# boron-v1_00.net
KiCad netlist of a schematic drawn in EAGLE
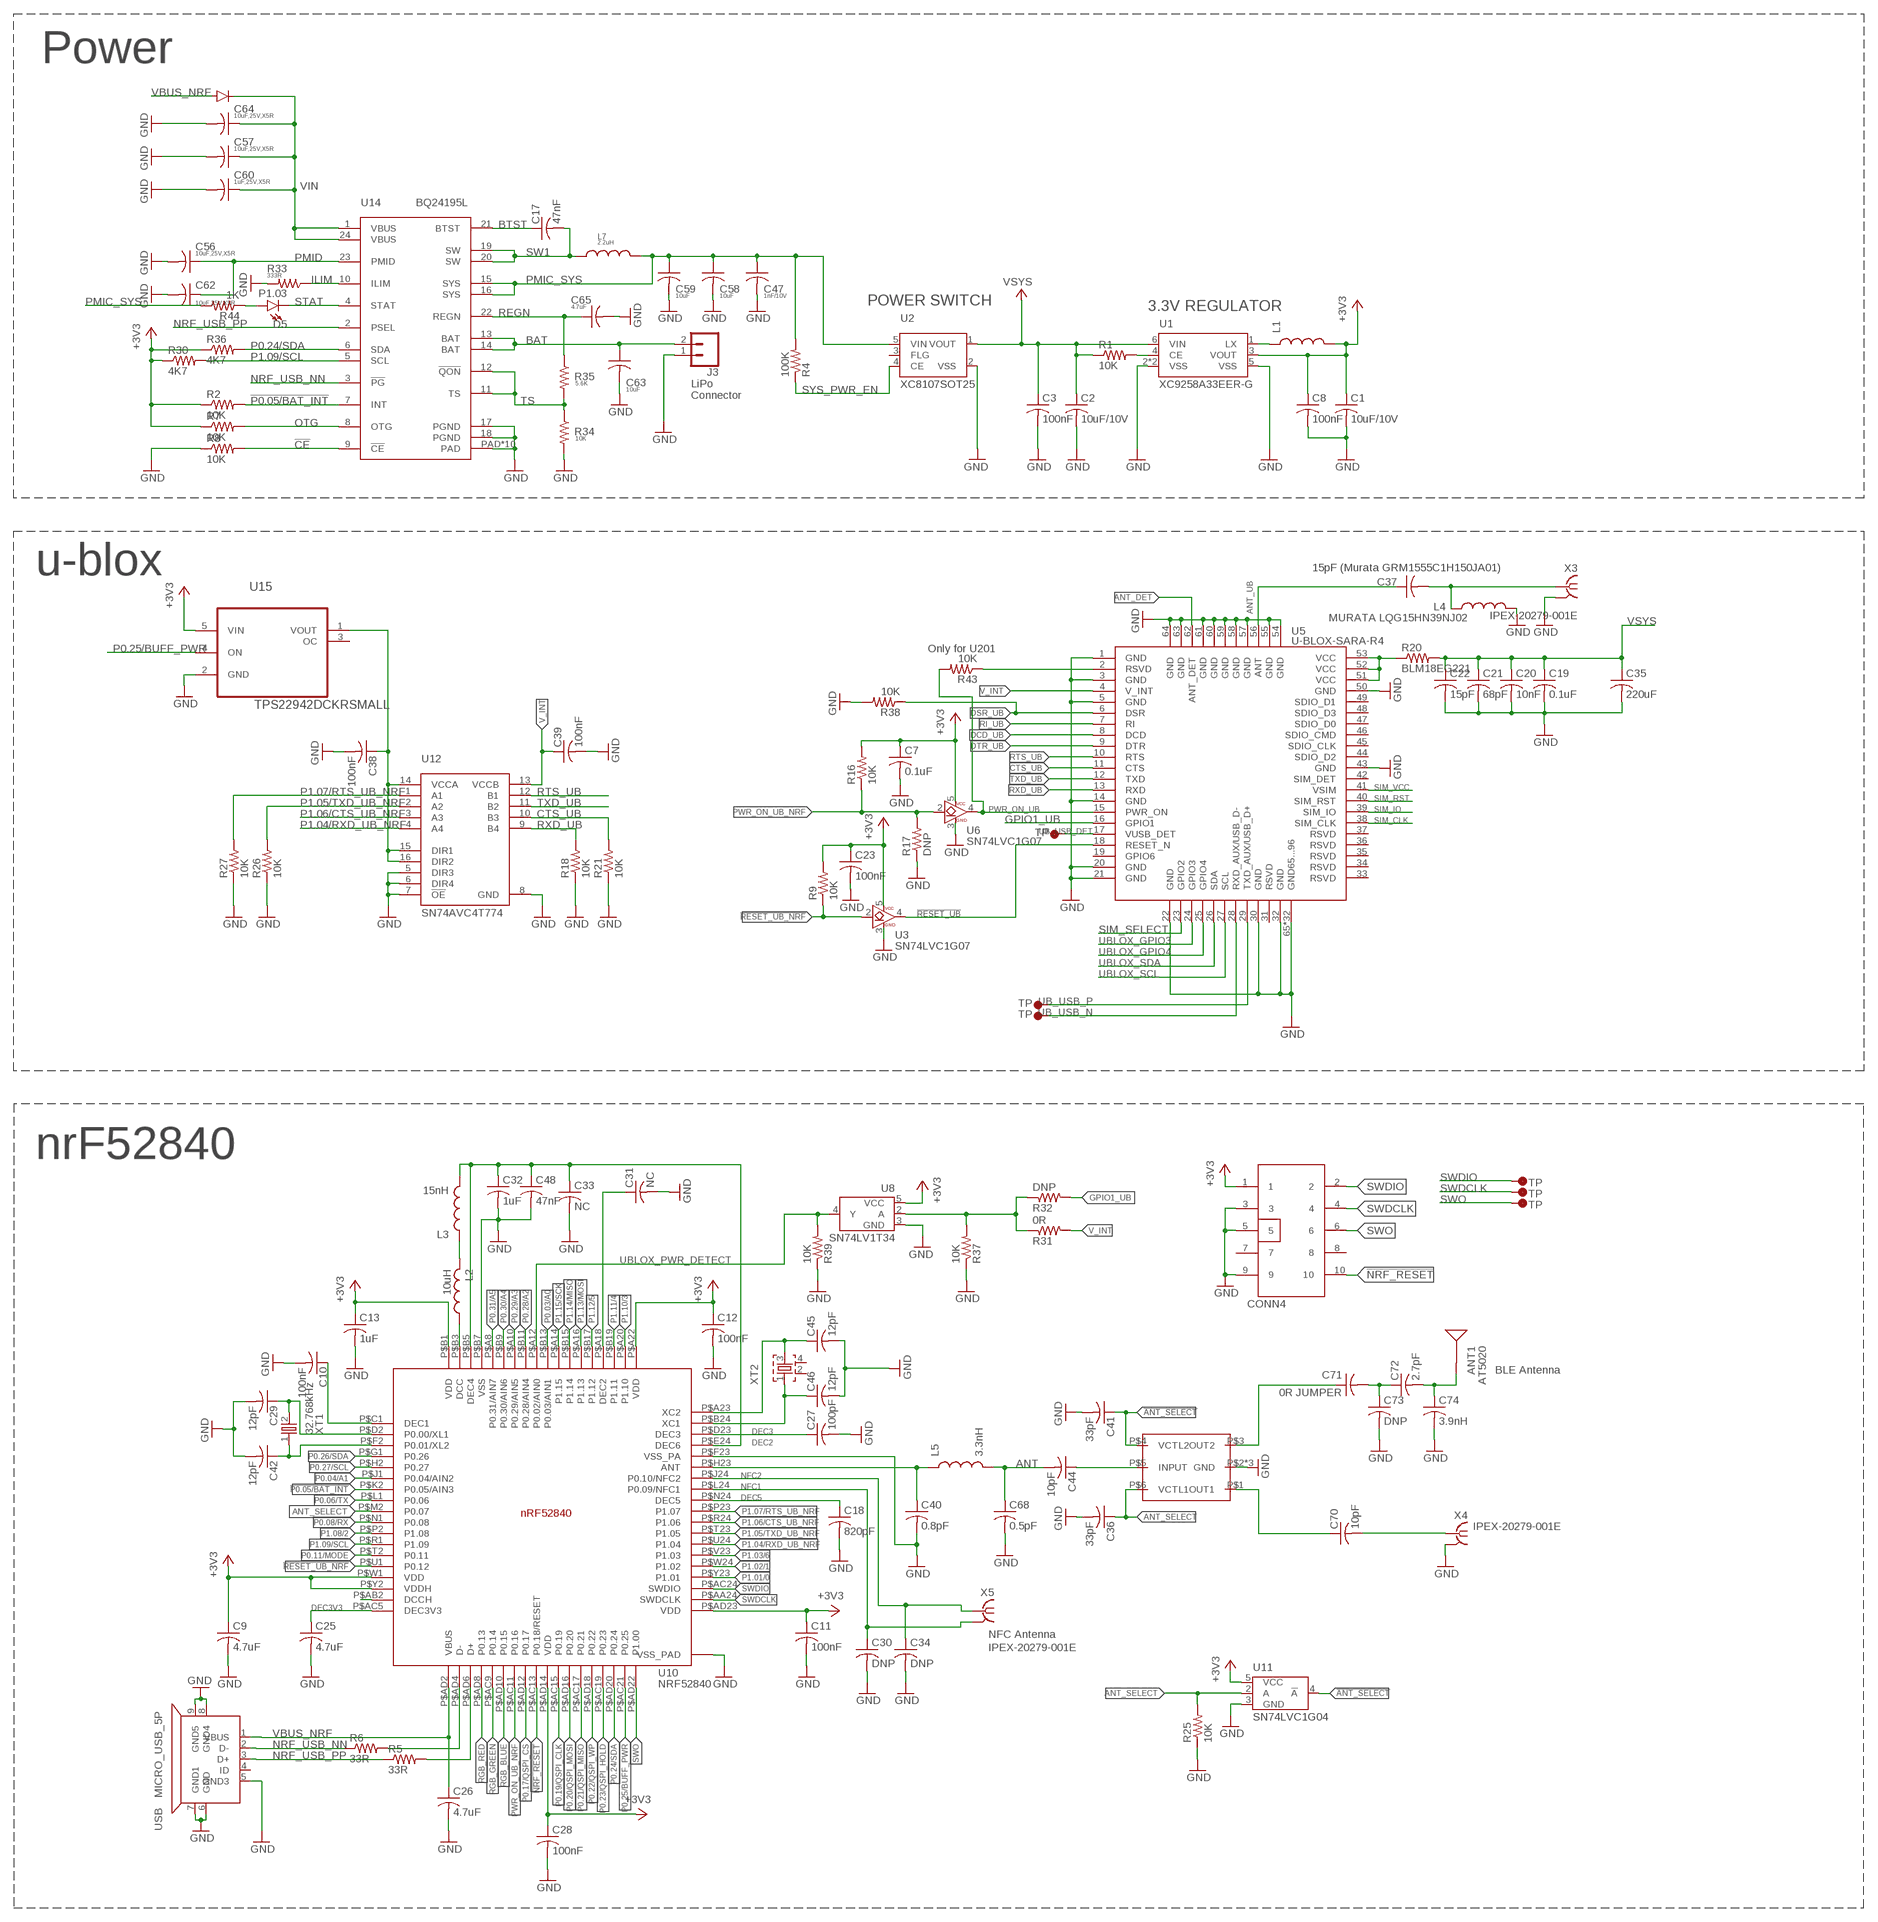
[diagram p0: schematic, sheet 1, part 1 of 2]
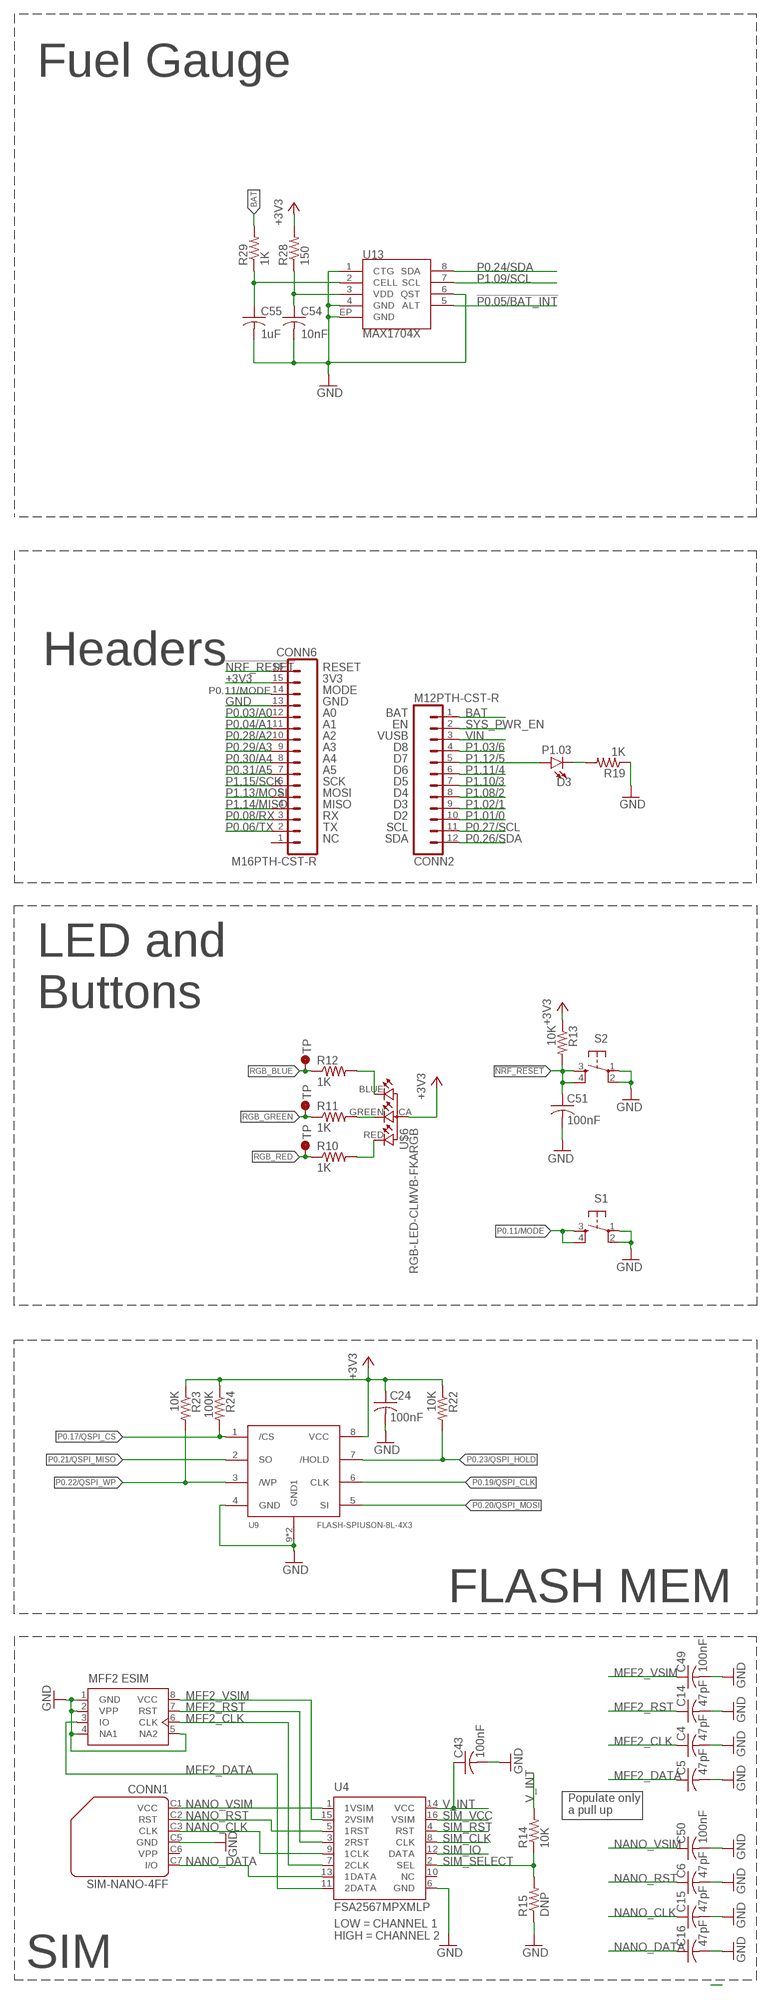
[diagram p1: schematic, sheet 1, part 2 of 2]

(export (version "E")
  (design (tool "Eeschema 10.0.6"))
  (components
    (comp (ref "ANT1")
      (value "AT5020")
      (footprint "eagle-import:AT5020")
      (libsource (lib "eagle-import") (part "AT5020"))
    )
    (comp (ref "C1")
      (value "10uF/10V")
      (footprint "eagle-import:C0603K")
      (libsource (lib "eagle-import") (part "C-USC0603K"))
    )
    (comp (ref "C2")
      (value "10uF/10V")
      (footprint "eagle-import:C0603K")
      (libsource (lib "eagle-import") (part "C-USC0603K"))
    )
    (comp (ref "C3")
      (value "100nF")
      (footprint "eagle-import:C0603K")
      (libsource (lib "eagle-import") (part "C-USC0603K"))
    )
    (comp (ref "C4")
      (value "47pF")
      (footprint "eagle-import:C0201_B")
      (libsource (lib "eagle-import") (part "C-USC0201_B"))
    )
    (comp (ref "C5")
      (value "47pF")
      (footprint "eagle-import:C0201_B")
      (libsource (lib "eagle-import") (part "C-USC0201_B"))
    )
    (comp (ref "C6")
      (value "47pF")
      (footprint "eagle-import:C0201_B")
      (libsource (lib "eagle-import") (part "C-USC0201_B"))
    )
    (comp (ref "C7")
      (value "0.1uF")
      (footprint "eagle-import:C0402_B")
      (libsource (lib "eagle-import") (part "Spark_C-US"))
    )
    (comp (ref "C8")
      (value "100nF")
      (footprint "eagle-import:C0201_B")
      (libsource (lib "eagle-import") (part "C-USC0201_B"))
    )
    (comp (ref "C9")
      (value "4.7uF")
      (footprint "eagle-import:C0402")
      (libsource (lib "eagle-import") (part "C-USC0402"))
    )
    (comp (ref "C10")
      (value "100nF")
      (footprint "eagle-import:C0201_B")
      (libsource (lib "eagle-import") (part "C-USC0201_B"))
    )
    (comp (ref "C11")
      (value "100nF")
      (footprint "eagle-import:C0201_B")
      (libsource (lib "eagle-import") (part "C-USC0201_B"))
    )
    (comp (ref "C12")
      (value "100nF")
      (footprint "eagle-import:C0201_B")
      (libsource (lib "eagle-import") (part "C-USC0201_B"))
    )
    (comp (ref "C13")
      (value "1uF")
      (footprint "eagle-import:C0402")
      (libsource (lib "eagle-import") (part "C-USC0402"))
    )
    (comp (ref "C14")
      (value "47pF")
      (footprint "eagle-import:C0201_B")
      (libsource (lib "eagle-import") (part "C-USC0201_B"))
    )
    (comp (ref "C15")
      (value "47pF")
      (footprint "eagle-import:C0201_B")
      (libsource (lib "eagle-import") (part "C-USC0201_B"))
    )
    (comp (ref "C16")
      (value "47pF")
      (footprint "eagle-import:C0201_B")
      (libsource (lib "eagle-import") (part "C-USC0201_B"))
    )
    (comp (ref "C17")
      (value "47nF")
      (footprint "eagle-import:C0201_B")
      (libsource (lib "eagle-import") (part "C-USC0201_B"))
    )
    (comp (ref "C18")
      (value "820pF")
      (footprint "eagle-import:C0201_B")
      (libsource (lib "eagle-import") (part "C-USC0201_B"))
    )
    (comp (ref "C19")
      (value "0.1uF")
      (footprint "eagle-import:C0402_B")
      (libsource (lib "eagle-import") (part "Spark_C-US"))
    )
    (comp (ref "C20")
      (value "10nF")
      (footprint "eagle-import:C0402_B")
      (libsource (lib "eagle-import") (part "Spark_C-US"))
    )
    (comp (ref "C21")
      (value "68pF")
      (footprint "eagle-import:C0402_B")
      (libsource (lib "eagle-import") (part "Spark_C-US"))
    )
    (comp (ref "C22")
      (value "15pF")
      (footprint "eagle-import:C0402_B")
      (libsource (lib "eagle-import") (part "Spark_C-US"))
    )
    (comp (ref "C23")
      (value "100nF")
      (footprint "eagle-import:C0201_B")
      (libsource (lib "eagle-import") (part "C-USC0201_B"))
    )
    (comp (ref "C24")
      (value "100nF")
      (footprint "eagle-import:C0201_B")
      (libsource (lib "eagle-import") (part "C-USC0201_B"))
    )
    (comp (ref "C25")
      (value "4.7uF")
      (footprint "eagle-import:C0402")
      (libsource (lib "eagle-import") (part "C-USC0402"))
    )
    (comp (ref "C26")
      (value "4.7uF")
      (footprint "eagle-import:C0402")
      (libsource (lib "eagle-import") (part "C-USC0402"))
    )
    (comp (ref "C27")
      (value "100pF")
      (footprint "eagle-import:C0201_B")
      (libsource (lib "eagle-import") (part "C-USC0201_B"))
    )
    (comp (ref "C28")
      (value "100nF")
      (footprint "eagle-import:C0201_B")
      (libsource (lib "eagle-import") (part "C-USC0201_B"))
    )
    (comp (ref "C29")
      (value "12pF")
      (footprint "eagle-import:C0201_B")
      (libsource (lib "eagle-import") (part "C-USC0201_B"))
    )
    (comp (ref "C30")
      (value "DNP")
      (footprint "eagle-import:C0201_B")
      (libsource (lib "eagle-import") (part "C-USC0201_B"))
    )
    (comp (ref "C31")
      (value "NC")
      (footprint "eagle-import:C0201_B")
      (libsource (lib "eagle-import") (part "C-USC0201_B"))
    )
    (comp (ref "C32")
      (value "1uF")
      (footprint "eagle-import:C0402K")
      (libsource (lib "eagle-import") (part "C-USC0402K"))
    )
    (comp (ref "C33")
      (value "NC")
      (footprint "eagle-import:C0201_B")
      (libsource (lib "eagle-import") (part "C-USC0201_B"))
    )
    (comp (ref "C34")
      (value "DNP")
      (footprint "eagle-import:C0201_B")
      (libsource (lib "eagle-import") (part "C-USC0201_B"))
    )
    (comp (ref "C35")
      (value "220uF")
      (footprint "eagle-import:C1210")
      (libsource (lib "eagle-import") (part "C-USC1210"))
    )
    (comp (ref "C36")
      (value "33pF")
      (footprint "eagle-import:C0201_B")
      (libsource (lib "eagle-import") (part "C-USC0201_B"))
    )
    (comp (ref "C37")
      (value "15pF (Murata GRM1555C1H150JA01)")
      (footprint "eagle-import:C0402_B")
      (libsource (lib "eagle-import") (part "Spark_C-US"))
    )
    (comp (ref "C38")
      (value "100nF")
      (footprint "eagle-import:C0201_B")
      (libsource (lib "eagle-import") (part "C-USC0201_B"))
    )
    (comp (ref "C39")
      (value "100nF")
      (footprint "eagle-import:C0201_B")
      (libsource (lib "eagle-import") (part "C-USC0201_B"))
    )
    (comp (ref "C40")
      (value "0.8pF")
      (footprint "eagle-import:C0201_B")
      (libsource (lib "eagle-import") (part "C-USC0201_B"))
    )
    (comp (ref "C41")
      (value "33pF")
      (footprint "eagle-import:C0201_B")
      (libsource (lib "eagle-import") (part "C-USC0201_B"))
    )
    (comp (ref "C42")
      (value "12pF")
      (footprint "eagle-import:C0201_B")
      (libsource (lib "eagle-import") (part "C-USC0201_B"))
    )
    (comp (ref "C43")
      (value "100nF")
      (footprint "eagle-import:C0201_B")
      (libsource (lib "eagle-import") (part "C-USC0201_B"))
    )
    (comp (ref "C44")
      (value "10pF")
      (footprint "eagle-import:C0201_B")
      (libsource (lib "eagle-import") (part "C-USC0201_B"))
    )
    (comp (ref "C45")
      (value "12pF")
      (footprint "eagle-import:C0201_B")
      (libsource (lib "eagle-import") (part "C-USC0201_B"))
    )
    (comp (ref "C46")
      (value "12pF")
      (footprint "eagle-import:C0201_B")
      (libsource (lib "eagle-import") (part "C-USC0201_B"))
    )
    (comp (ref "C47")
      (value "1nF/10V")
      (footprint "eagle-import:C0402_B")
      (libsource (lib "eagle-import") (part "C-US0402"))
    )
    (comp (ref "C48")
      (value "47nF")
      (footprint "eagle-import:C0201_B")
      (libsource (lib "eagle-import") (part "C-USC0201_B"))
    )
    (comp (ref "C49")
      (value "100nF")
      (footprint "eagle-import:C0201_B")
      (libsource (lib "eagle-import") (part "C-USC0201_B"))
    )
    (comp (ref "C50")
      (value "100nF")
      (footprint "eagle-import:C0201_B")
      (libsource (lib "eagle-import") (part "C-USC0201_B"))
    )
    (comp (ref "C51")
      (value "100nF")
      (footprint "eagle-import:C0201_B")
      (libsource (lib "eagle-import") (part "C-USC0201_B"))
    )
    (comp (ref "C54")
      (value "10nF")
      (footprint "eagle-import:C0402_B")
      (libsource (lib "eagle-import") (part "Spark_C-US"))
    )
    (comp (ref "C55")
      (value "1uF")
      (footprint "eagle-import:C0402_B")
      (libsource (lib "eagle-import") (part "Spark_C-US"))
    )
    (comp (ref "C56")
      (value "10uF,25V,X5R")
      (footprint "eagle-import:C0603_B")
      (libsource (lib "eagle-import") (part "C-US0603"))
    )
    (comp (ref "C57")
      (value "10uF,25V,X5R")
      (footprint "eagle-import:C0603_B")
      (libsource (lib "eagle-import") (part "C-US0603"))
    )
    (comp (ref "C58")
      (value "10uF")
      (footprint "eagle-import:C0603_B")
      (libsource (lib "eagle-import") (part "C-US0603"))
    )
    (comp (ref "C59")
      (value "10uF")
      (footprint "eagle-import:C0603_B")
      (libsource (lib "eagle-import") (part "C-US0603"))
    )
    (comp (ref "C60")
      (value "1uF,25V,X5R")
      (footprint "eagle-import:C0603_B")
      (libsource (lib "eagle-import") (part "C-US0603"))
    )
    (comp (ref "C62")
      (value "10uF,25V,X5R")
      (footprint "eagle-import:C0603_B")
      (libsource (lib "eagle-import") (part "C-US0603"))
    )
    (comp (ref "C63")
      (value "10uF")
      (footprint "eagle-import:C0603_B")
      (libsource (lib "eagle-import") (part "C-US0603"))
    )
    (comp (ref "C64")
      (value "10uF,25V,X5R")
      (footprint "eagle-import:C0603_B")
      (libsource (lib "eagle-import") (part "C-US0603"))
    )
    (comp (ref "C65")
      (value "4.7uF")
      (footprint "eagle-import:C0603_B")
      (libsource (lib "eagle-import") (part "C-US0603"))
    )
    (comp (ref "C68")
      (value "0.5pF")
      (footprint "eagle-import:C0201_B")
      (libsource (lib "eagle-import") (part "C-USC0201_B"))
    )
    (comp (ref "C70")
      (value "10pF")
      (footprint "eagle-import:C0201_B")
      (libsource (lib "eagle-import") (part "C-USC0201_B"))
    )
    (comp (ref "C71")
      (value "0R JUMPER")
      (footprint "eagle-import:C0201_B")
      (libsource (lib "eagle-import") (part "C-USC0201_B"))
    )
    (comp (ref "C72")
      (value "2.7pF")
      (footprint "eagle-import:C0201_B")
      (libsource (lib "eagle-import") (part "C-USC0201_B"))
    )
    (comp (ref "C73")
      (value "DNP")
      (footprint "eagle-import:C0201_B")
      (libsource (lib "eagle-import") (part "C-USC0201_B"))
    )
    (comp (ref "C74")
      (value "3.9nH")
      (footprint "eagle-import:C0201_B")
      (libsource (lib "eagle-import") (part "C-USC0201_B"))
    )
    (comp (ref "CONN1")
      (value "SIM-NANO-4FF")
      (footprint "eagle-import:GCT-SIM8100")
      (libsource (lib "eagle-import") (part "SIM-NANO-4FF"))
    )
    (comp (ref "CONN2")
      (value "M12PTH-CST-R")
      (footprint "eagle-import:1X12-CASTELLATED")
      (libsource (lib "eagle-import") (part "M12PTH-CST-R"))
    )
    (comp (ref "CONN4")
      (value "CONN5X2")
      (footprint "eagle-import:CONN5X2_1.27")
      (libsource (lib "eagle-import") (part "CONN5X2"))
    )
    (comp (ref "CONN6")
      (value "M16PTH-CST-R")
      (footprint "eagle-import:1X16-CASTELLATED")
      (libsource (lib "eagle-import") (part "M16PTH-CST-R"))
    )
    (comp (ref "D3")
      (value "P1.03")
      (footprint "eagle-import:LED-0603")
      (libsource (lib "eagle-import") (part "LED-RED0603"))
    )
    (comp (ref "D4")
      (value "DIODE_NT")
      (footprint "eagle-import:DIODE-DO-220AA_NT(SMP)")
      (libsource (lib "eagle-import") (part "DIODE_NT"))
    )
    (comp (ref "D5")
      (value "P1.03")
      (footprint "eagle-import:LED-0603")
      (libsource (lib "eagle-import") (part "LED-RED0603"))
    )
    (comp (ref "J3")
      (value "CONN_02-JST-2MM-SMT")
      (footprint "eagle-import:JST-2-SMD@2")
      (libsource (lib "eagle-import") (part "CONN_02-JST-2MM-SMT"))
    )
    (comp (ref "L1")
      (value "INDUCTOR-SPARKFUNVLS3012ET-4R7M")
      (footprint "eagle-import:INDUCTOR-VLS-E")
      (libsource (lib "eagle-import") (part "INDUCTOR-SPARKFUNVLS3012ET-4R7M"))
    )
    (comp (ref "L2")
      (value "10uH")
      (footprint "eagle-import:RESC0603_L")
      (libsource (lib "eagle-import") (part "INDUCTOR_0603_L"))
    )
    (comp (ref "L3")
      (value "15nH")
      (footprint "eagle-import:C0402_B")
      (libsource (lib "eagle-import") (part "INDUCTOR-0402"))
    )
    (comp (ref "L4")
      (value "MURATA LQG15HN39NJ02")
      (footprint "eagle-import:C0402_B")
      (libsource (lib "eagle-import") (part "INDUCTOR-0402"))
    )
    (comp (ref "L5")
      (value "3.3nH")
      (footprint "eagle-import:C0402_B")
      (libsource (lib "eagle-import") (part "INDUCTOR-0402"))
    )
    (comp (ref "L7")
      (value "2.2uH")
      (footprint "eagle-import:INDUCTOR-4040")
      (libsource (lib "eagle-import") (part "INDUCTORI"))
    )
    (comp (ref "R1")
      (value "10K")
      (footprint "eagle-import:C0201_B")
      (libsource (lib "eagle-import") (part "R-US_R0201_B"))
    )
    (comp (ref "R2")
      (value "10K")
      (footprint "eagle-import:C0201_B")
      (libsource (lib "eagle-import") (part "R-US_R0201_B"))
    )
    (comp (ref "R4")
      (value "100K")
      (footprint "eagle-import:C0201_B")
      (libsource (lib "eagle-import") (part "R-US_R0201_B"))
    )
    (comp (ref "R5")
      (value "33R")
      (footprint "eagle-import:C0201_B")
      (libsource (lib "eagle-import") (part "R-US_R0201_B"))
    )
    (comp (ref "R6")
      (value "33R")
      (footprint "eagle-import:C0201_B")
      (libsource (lib "eagle-import") (part "R-US_R0201_B"))
    )
    (comp (ref "R7")
      (value "10K")
      (footprint "eagle-import:C0201_B")
      (libsource (lib "eagle-import") (part "R-US_R0201_B"))
    )
    (comp (ref "R8")
      (value "10K")
      (footprint "eagle-import:C0201_B")
      (libsource (lib "eagle-import") (part "R-US_R0201_B"))
    )
    (comp (ref "R9")
      (value "10K")
      (footprint "eagle-import:C0201_B")
      (libsource (lib "eagle-import") (part "R-US_R0201_B"))
    )
    (comp (ref "R10")
      (value "1K")
      (footprint "eagle-import:C0201_B")
      (libsource (lib "eagle-import") (part "R-US_R0201_B"))
    )
    (comp (ref "R11")
      (value "1K")
      (footprint "eagle-import:C0201_B")
      (libsource (lib "eagle-import") (part "R-US_R0201_B"))
    )
    (comp (ref "R12")
      (value "1K")
      (footprint "eagle-import:C0201_B")
      (libsource (lib "eagle-import") (part "R-US_R0201_B"))
    )
    (comp (ref "R13")
      (value "10K")
      (footprint "eagle-import:C0201_B")
      (libsource (lib "eagle-import") (part "R-US_R0201_B"))
    )
    (comp (ref "R14")
      (value "10K")
      (footprint "eagle-import:C0201_B")
      (libsource (lib "eagle-import") (part "R-US_R0201_B"))
    )
    (comp (ref "R15")
      (value "DNP")
      (footprint "eagle-import:C0201_B")
      (libsource (lib "eagle-import") (part "R-US_R0201_B"))
    )
    (comp (ref "R16")
      (value "10K")
      (footprint "eagle-import:C0201_B")
      (libsource (lib "eagle-import") (part "R-US_R0201_B"))
    )
    (comp (ref "R17")
      (value "DNP")
      (footprint "eagle-import:C0201_B")
      (libsource (lib "eagle-import") (part "R-US_R0201_B"))
    )
    (comp (ref "R18")
      (value "10K")
      (footprint "eagle-import:C0201_B")
      (libsource (lib "eagle-import") (part "R-US_R0201_B"))
    )
    (comp (ref "R19")
      (value "1K")
      (footprint "eagle-import:C0201_B")
      (libsource (lib "eagle-import") (part "R-US_R0201_B"))
    )
    (comp (ref "R20")
      (value "BLM18EG221")
      (footprint "eagle-import:R0603")
      (libsource (lib "eagle-import") (part "R-US_R0603"))
    )
    (comp (ref "R21")
      (value "10K")
      (footprint "eagle-import:C0201_B")
      (libsource (lib "eagle-import") (part "R-US_R0201_B"))
    )
    (comp (ref "R22")
      (value "10K")
      (footprint "eagle-import:C0201_B")
      (libsource (lib "eagle-import") (part "R-US_R0201_B"))
    )
    (comp (ref "R23")
      (value "10K")
      (footprint "eagle-import:C0201_B")
      (libsource (lib "eagle-import") (part "R-US_R0201_B"))
    )
    (comp (ref "R24")
      (value "100K")
      (footprint "eagle-import:C0201_B")
      (libsource (lib "eagle-import") (part "R-US_R0201_B"))
    )
    (comp (ref "R25")
      (value "10K")
      (footprint "eagle-import:C0201_B")
      (libsource (lib "eagle-import") (part "R-US_R0201_B"))
    )
    (comp (ref "R26")
      (value "10K")
      (footprint "eagle-import:C0201_B")
      (libsource (lib "eagle-import") (part "R-US_R0201_B"))
    )
    (comp (ref "R27")
      (value "10K")
      (footprint "eagle-import:C0201_B")
      (libsource (lib "eagle-import") (part "R-US_R0201_B"))
    )
    (comp (ref "R28")
      (value "150")
      (footprint "eagle-import:0402-RES")
      (libsource (lib "eagle-import") (part "RESISTOR0402-RES"))
    )
    (comp (ref "R29")
      (value "1K")
      (footprint "eagle-import:0402-RES")
      (libsource (lib "eagle-import") (part "RESISTOR0402-RES"))
    )
    (comp (ref "R30")
      (value "4K7")
      (footprint "eagle-import:C0201_B")
      (libsource (lib "eagle-import") (part "R-US_R0201_B"))
    )
    (comp (ref "R31")
      (value "0R")
      (footprint "eagle-import:C0201_B")
      (libsource (lib "eagle-import") (part "R-US_R0201_B"))
    )
    (comp (ref "R32")
      (value "DNP")
      (footprint "eagle-import:C0201_B")
      (libsource (lib "eagle-import") (part "R-US_R0201_B"))
    )
    (comp (ref "R33")
      (value "333R")
      (footprint "eagle-import:R0402_B")
      (libsource (lib "eagle-import") (part "Spark_R-US_"))
    )
    (comp (ref "R34")
      (value "10K")
      (footprint "eagle-import:R0402_B")
      (libsource (lib "eagle-import") (part "Spark_R-US_"))
    )
    (comp (ref "R35")
      (value "5.6K")
      (footprint "eagle-import:R0402_B")
      (libsource (lib "eagle-import") (part "Spark_R-US_"))
    )
    (comp (ref "R36")
      (value "4K7")
      (footprint "eagle-import:C0201_B")
      (libsource (lib "eagle-import") (part "R-US_R0201_B"))
    )
    (comp (ref "R37")
      (value "10K")
      (footprint "eagle-import:C0201_B")
      (libsource (lib "eagle-import") (part "R-US_R0201_B"))
    )
    (comp (ref "R38")
      (value "10K")
      (footprint "eagle-import:C0201_B")
      (libsource (lib "eagle-import") (part "R-US_R0201_B"))
    )
    (comp (ref "R39")
      (value "10K")
      (footprint "eagle-import:C0201_B")
      (libsource (lib "eagle-import") (part "R-US_R0201_B"))
    )
    (comp (ref "R43")
      (value "10K")
      (footprint "eagle-import:C0201_B")
      (libsource (lib "eagle-import") (part "R-US_R0201_B"))
    )
    (comp (ref "R44")
      (value "1K")
      (footprint "eagle-import:C0201_B")
      (libsource (lib "eagle-import") (part "R-US_R0201_B"))
    )
    (comp (ref "S1")
      (value "TAC_SWITCHSMD")
      (footprint "eagle-import:TACTILE_SWITCH_SMD")
      (libsource (lib "eagle-import") (part "TAC_SWITCHSMD"))
    )
    (comp (ref "S2")
      (value "TAC_SWITCHSMD")
      (footprint "eagle-import:TACTILE_SWITCH_SMD")
      (libsource (lib "eagle-import") (part "TAC_SWITCHSMD"))
    )
    (comp (ref "U$1")
      (value "TP5")
      (footprint "eagle-import:TP30_TOP")
      (libsource (lib "eagle-import") (part "TP5"))
    )
    (comp (ref "U$4")
      (value "TP5")
      (footprint "eagle-import:TP30_TOP")
      (libsource (lib "eagle-import") (part "TP5"))
    )
    (comp (ref "U$5")
      (value "TP5")
      (footprint "eagle-import:TP30_TOP")
      (libsource (lib "eagle-import") (part "TP5"))
    )
    (comp (ref "U$6")
      (value "RGB-LED-CLMVB-FKARGB")
      (footprint "eagle-import:PLCC4-2MM-RGB")
      (libsource (lib "eagle-import") (part "RGB-LED-CLMVB-FKARGB"))
    )
    (comp (ref "U$7")
      (value "SKY13351-378LF")
      (footprint "eagle-import:MLPD-6-1X1")
      (libsource (lib "eagle-import") (part "SKY13351-378LF"))
    )
    (comp (ref "U$9")
      (value "TP5")
      (footprint "eagle-import:TP30_TOP")
      (libsource (lib "eagle-import") (part "TP5"))
    )
    (comp (ref "U$10")
      (value "TP5")
      (footprint "eagle-import:TP30_TOP")
      (libsource (lib "eagle-import") (part "TP5"))
    )
    (comp (ref "U$11")
      (value "TP5")
      (footprint "eagle-import:TP30_TOP")
      (libsource (lib "eagle-import") (part "TP5"))
    )
    (comp (ref "U$18")
      (value "TP5")
      (footprint "eagle-import:TP30_TOP")
      (libsource (lib "eagle-import") (part "TP5"))
    )
    (comp (ref "U$19")
      (value "TP5")
      (footprint "eagle-import:TP30_TOP")
      (libsource (lib "eagle-import") (part "TP5"))
    )
    (comp (ref "U$20")
      (value "TP5")
      (footprint "eagle-import:TP30_TOP")
      (libsource (lib "eagle-import") (part "TP5"))
    )
    (comp (ref "U1")
      (value "XC9258A33EER-G")
      (footprint "eagle-import:USP-6C")
      (libsource (lib "eagle-import") (part "XC9258A33EER-G"))
    )
    (comp (ref "U2")
      (value "XC8107SOT25")
      (footprint "eagle-import:SOT25")
      (libsource (lib "eagle-import") (part "XC8107SOT25"))
    )
    (comp (ref "U3")
      (value "SN74LVC1G07")
      (footprint "eagle-import:SC-70-5")
      (libsource (lib "eagle-import") (part "SN74LVC1G07"))
    )
    (comp (ref "U4")
      (value "FSA2567MPXMLP")
      (footprint "eagle-import:MLP16")
      (libsource (lib "eagle-import") (part "FSA2567MPXMLP"))
    )
    (comp (ref "U5")
      (value "U-BLOX-SARA-R4")
      (footprint "eagle-import:U-BLOX-SARA-U2")
      (libsource (lib "eagle-import") (part "U-BLOX-SARA-R4"))
    )
    (comp (ref "U6")
      (value "SN74LVC1G07")
      (footprint "eagle-import:SC-70-5")
      (libsource (lib "eagle-import") (part "SN74LVC1G07"))
    )
    (comp (ref "U7")
      (value "ESIMSON8")
      (footprint "eagle-import:MFF2")
      (libsource (lib "eagle-import") (part "ESIMSON8"))
    )
    (comp (ref "U8")
      (value "SN74LV1T34")
      (footprint "eagle-import:SC70-5")
      (libsource (lib "eagle-import") (part "SN74LV1T34"))
    )
    (comp (ref "U9")
      (value "FLASH-SPIUSON-8L-4X3")
      (footprint "eagle-import:USON8-3X4")
      (libsource (lib "eagle-import") (part "FLASH-SPIUSON-8L-4X3"))
    )
    (comp (ref "U10")
      (value "NRF52840")
      (footprint "eagle-import:AQFN50P700X700X85_HS-74N")
      (libsource (lib "eagle-import") (part "NRF52840"))
    )
    (comp (ref "U11")
      (value "SN74LVC1G04")
      (footprint "eagle-import:SC70-5")
      (libsource (lib "eagle-import") (part "SN74LVC1G04"))
    )
    (comp (ref "U12")
      (value "SN74AVC4T774")
      (footprint "eagle-import:UFQFN-16")
      (libsource (lib "eagle-import") (part "SN74AVC4T774"))
    )
    (comp (ref "U13")
      (value "MAX1704X")
      (footprint "eagle-import:TDFN-8")
      (libsource (lib "eagle-import") (part "MAX1704X"))
    )
    (comp (ref "U14")
      (value "BQ24195L")
      (footprint "eagle-import:QFN24")
      (libsource (lib "eagle-import") (part "BQ24298RTWR"))
    )
    (comp (ref "U15")
      (value "TPS22942DCKRSMALL")
      (footprint "eagle-import:SC70-5")
      (libsource (lib "eagle-import") (part "TPS22942DCKRSMALL"))
    )
    (comp (ref "USB")
      (value "MICRO_USB_5P")
      (footprint "eagle-import:MICRO_USB")
      (libsource (lib "eagle-import") (part "MICRO_USBMICRO_USB"))
    )
    (comp (ref "X3")
      (value "IPEX-20279-001E")
      (footprint "eagle-import:IPEX-20279-001E")
      (libsource (lib "eagle-import") (part "Spark_IPEX-20279-001E"))
    )
    (comp (ref "X4")
      (value "IPEX-20279-001E")
      (footprint "eagle-import:IPEX-20279-001E")
      (libsource (lib "eagle-import") (part "IPEX-20279-001E"))
    )
    (comp (ref "X5")
      (value "IPEX-20279-001E")
      (footprint "eagle-import:IPEX-20279-001E")
      (libsource (lib "eagle-import") (part "IPEX-20279-001E"))
    )
    (comp (ref "XT1")
      (value "32.768kHz")
      (footprint "eagle-import:XTAL_3215_N")
      (libsource (lib "eagle-import") (part "XTAL_32KHZ"))
    )
    (comp (ref "XT2")
      (value "XTAL_32MHZ")
      (footprint "eagle-import:BT-XTAL_2016_N")
      (libsource (lib "eagle-import") (part "XTAL_32MHZ"))
    )
  )
  (nets
    (net (code "1") (name "+3V3") (class "Default")
      (node (ref "C1") (pin "1") (pinfunction "1_1") (pintype "passive"))
      (node (ref "C11") (pin "1") (pinfunction "1_1") (pintype "passive"))
      (node (ref "C12") (pin "1") (pinfunction "1_1") (pintype "passive"))
      (node (ref "C13") (pin "1") (pinfunction "1_1") (pintype "passive"))
      (node (ref "C23") (pin "1") (pinfunction "1_1") (pintype "passive"))
      (node (ref "C24") (pin "1") (pinfunction "1_1") (pintype "passive"))
      (node (ref "C28") (pin "1") (pinfunction "1_1") (pintype "passive"))
      (node (ref "C7") (pin "1") (pinfunction "1_1") (pintype "passive"))
      (node (ref "C8") (pin "1") (pinfunction "1_1") (pintype "passive"))
      (node (ref "C9") (pin "1") (pinfunction "1_1") (pintype "passive"))
      (node (ref "CONN4") (pin "1") (pinfunction "1_1") (pintype "bidirectional"))
      (node (ref "CONN6") (pin "15") (pinfunction "15_15") (pintype "passive"))
      (node (ref "L1") (pin "P$2") (pinfunction "2_P$2") (pintype "passive"))
      (node (ref "R13") (pin "1") (pinfunction "1_1") (pintype "passive"))
      (node (ref "R16") (pin "2") (pinfunction "2_2") (pintype "passive"))
      (node (ref "R2") (pin "1") (pinfunction "1_1") (pintype "passive"))
      (node (ref "R22") (pin "1") (pinfunction "1_1") (pintype "passive"))
      (node (ref "R23") (pin "1") (pinfunction "1_1") (pintype "passive"))
      (node (ref "R24") (pin "1") (pinfunction "1_1") (pintype "passive"))
      (node (ref "R28") (pin "2") (pinfunction "2_2") (pintype "passive"))
      (node (ref "R30") (pin "1") (pinfunction "1_1") (pintype "passive"))
      (node (ref "R36") (pin "1") (pinfunction "1_1") (pintype "passive"))
      (node (ref "R7") (pin "1") (pinfunction "1_1") (pintype "passive"))
      (node (ref "R9") (pin "2") (pinfunction "2_2") (pintype "passive"))
      (node (ref "U$6") (pin "CA") (pinfunction "1_CA") (pintype "passive"))
      (node (ref "U1") (pin "3") (pinfunction "VOUT_3") (pintype "power_in"))
      (node (ref "U10") (pin "P$A22") (pinfunction "VDD_P$A22") (pintype "power_in"))
      (node (ref "U10") (pin "P$AD14") (pinfunction "VDD_P$AD14") (pintype "power_in"))
      (node (ref "U10") (pin "P$AD23") (pinfunction "VDD_P$AD23") (pintype "power_in"))
      (node (ref "U10") (pin "P$B1") (pinfunction "VDD_P$B1") (pintype "power_in"))
      (node (ref "U10") (pin "P$W1") (pinfunction "VDD_P$W1") (pintype "power_in"))
      (node (ref "U10") (pin "P$Y2") (pinfunction "VDDH_P$Y2") (pintype "power_in"))
      (node (ref "U11") (pin "5") (pinfunction "VCC_5") (pintype "power_in"))
      (node (ref "U15") (pin "5") (pinfunction "VIN_5") (pintype "power_in"))
      (node (ref "U3") (pin "5") (pinfunction "VCC_5") (pintype "bidirectional"))
      (node (ref "U6") (pin "5") (pinfunction "VCC_5") (pintype "bidirectional"))
      (node (ref "U8") (pin "5") (pinfunction "VCC_5") (pintype "power_in"))
      (node (ref "U9") (pin "8") (pinfunction "VCC_8") (pintype "bidirectional"))
    )
    (net (code "2") (name "/ANT") (class "Default")
      (node (ref "C44") (pin "2") (pinfunction "2_2") (pintype "passive"))
      (node (ref "C68") (pin "1") (pinfunction "1_1") (pintype "passive"))
      (node (ref "L5") (pin "2") (pinfunction "2_2") (pintype "passive"))
    )
    (net (code "3") (name "/ANT_UB") (class "Default")
      (node (ref "C37") (pin "1") (pinfunction "1_1") (pintype "passive"))
      (node (ref "U5") (pin "56") (pinfunction "ANT_56") (pintype "bidirectional"))
    )
    (net (code "4") (name "/BTST") (class "Default")
      (node (ref "C17") (pin "1") (pinfunction "1_1") (pintype "passive"))
      (node (ref "U14") (pin "21") (pinfunction "BTST_21") (pintype "bidirectional"))
    )
    (net (code "5") (name "/DEC2") (class "Default")
      (node (ref "C32") (pin "1") (pinfunction "1_1") (pintype "passive"))
      (node (ref "C33") (pin "1") (pinfunction "1_1") (pintype "passive"))
      (node (ref "C48") (pin "1") (pinfunction "1_1") (pintype "passive"))
      (node (ref "L3") (pin "2") (pinfunction "2_2") (pintype "passive"))
      (node (ref "U10") (pin "P$B5") (pinfunction "DEC4_P$B5") (pintype "power_in"))
      (node (ref "U10") (pin "P$E24") (pinfunction "DEC6_P$E24") (pintype "bidirectional"))
    )
    (net (code "6") (name "/DEC3") (class "Default")
      (node (ref "C27") (pin "1") (pinfunction "1_1") (pintype "passive"))
      (node (ref "U10") (pin "P$D23") (pinfunction "DEC3_P$D23") (pintype "bidirectional"))
    )
    (net (code "7") (name "/DEC3V3") (class "Default")
      (node (ref "C25") (pin "1") (pinfunction "1_1") (pintype "passive"))
      (node (ref "U10") (pin "P$AC5") (pinfunction "DEC3V3_P$AC5") (pintype "bidirectional"))
    )
    (net (code "8") (name "/DEC5") (class "Default")
      (node (ref "C18") (pin "1") (pinfunction "1_1") (pintype "passive"))
      (node (ref "U10") (pin "P$N24") (pinfunction "DEC5_P$N24") (pintype "bidirectional"))
    )
    (net (code "9") (name "/ILIM") (class "Default")
      (node (ref "R33") (pin "1") (pinfunction "1_1") (pintype "passive"))
      (node (ref "U14") (pin "10") (pinfunction "ILIM_10") (pintype "output"))
    )
    (net (code "10") (name "/MFF2_CLK") (class "Default")
      (node (ref "C4") (pin "1") (pinfunction "1_1") (pintype "passive"))
      (node (ref "U4") (pin "7") (pinfunction "2CLK_7") (pintype "bidirectional"))
      (node (ref "U7") (pin "6") (pinfunction "CLK_6") (pintype "bidirectional"))
    )
    (net (code "11") (name "/MFF2_DATA") (class "Default")
      (node (ref "C5") (pin "1") (pinfunction "1_1") (pintype "passive"))
      (node (ref "U4") (pin "11") (pinfunction "2DATA_11") (pintype "bidirectional"))
      (node (ref "U7") (pin "3") (pinfunction "IO_3") (pintype "bidirectional"))
    )
    (net (code "12") (name "/MFF2_RST") (class "Default")
      (node (ref "C14") (pin "1") (pinfunction "1_1") (pintype "passive"))
      (node (ref "U4") (pin "3") (pinfunction "2RST_3") (pintype "bidirectional"))
      (node (ref "U7") (pin "7") (pinfunction "RST_7") (pintype "bidirectional"))
    )
    (net (code "13") (name "/MFF2_VSIM") (class "Default")
      (node (ref "C49") (pin "1") (pinfunction "1_1") (pintype "passive"))
      (node (ref "U4") (pin "15") (pinfunction "2VSIM_15") (pintype "bidirectional"))
      (node (ref "U7") (pin "8") (pinfunction "VCC_8") (pintype "power_in"))
    )
    (net (code "14") (name "/NANO_CLK") (class "Default")
      (node (ref "C15") (pin "1") (pinfunction "1_1") (pintype "passive"))
      (node (ref "CONN1") (pin "C3") (pinfunction "CLK_C3") (pintype "passive"))
      (node (ref "U4") (pin "9") (pinfunction "1CLK_9") (pintype "bidirectional"))
    )
    (net (code "15") (name "/NANO_DATA") (class "Default")
      (node (ref "C16") (pin "1") (pinfunction "1_1") (pintype "passive"))
      (node (ref "CONN1") (pin "C7") (pinfunction "I/O_C7") (pintype "passive"))
      (node (ref "U4") (pin "13") (pinfunction "1DATA_13") (pintype "bidirectional"))
    )
    (net (code "16") (name "/NANO_RST") (class "Default")
      (node (ref "C6") (pin "1") (pinfunction "1_1") (pintype "passive"))
      (node (ref "CONN1") (pin "C2") (pinfunction "RST_C2") (pintype "passive"))
      (node (ref "U4") (pin "5") (pinfunction "1RST_5") (pintype "bidirectional"))
    )
    (net (code "17") (name "/NANO_VSIM") (class "Default")
      (node (ref "C50") (pin "1") (pinfunction "1_1") (pintype "passive"))
      (node (ref "CONN1") (pin "C1") (pinfunction "VCC_C1") (pintype "passive"))
      (node (ref "U4") (pin "1") (pinfunction "1VSIM_1") (pintype "bidirectional"))
    )
    (net (code "18") (name "/NFC1") (class "Default")
      (node (ref "C30") (pin "1") (pinfunction "1_1") (pintype "passive"))
      (node (ref "U10") (pin "P$L24") (pinfunction "P0.09/NFC1_P$L24") (pintype "bidirectional"))
      (node (ref "X5") (pin "2@1") (pinfunction "GND_2@1") (pintype "passive"))
      (node (ref "X5") (pin "2@2") (pinfunction "GND_2@2") (pintype "passive"))
    )
    (net (code "19") (name "/NFC2") (class "Default")
      (node (ref "C34") (pin "1") (pinfunction "1_1") (pintype "passive"))
      (node (ref "U10") (pin "P$J24") (pinfunction "P0.10/NFC2_P$J24") (pintype "bidirectional"))
      (node (ref "X5") (pin "1") (pinfunction "1_1") (pintype "passive"))
    )
    (net (code "20") (name "/NRF_USB_NN") (class "Default")
      (node (ref "R6") (pin "1") (pinfunction "1_1") (pintype "passive"))
      (node (ref "U14") (pin "3") (pinfunction "~{PG}_3") (pintype "output"))
      (node (ref "USB") (pin "2") (pinfunction "D-_2") (pintype "bidirectional"))
    )
    (net (code "21") (name "/NRF_USB_PP") (class "Default")
      (node (ref "R5") (pin "1") (pinfunction "1_1") (pintype "passive"))
      (node (ref "U14") (pin "2") (pinfunction "PSEL_2") (pintype "output"))
      (node (ref "USB") (pin "3") (pinfunction "D+_3") (pintype "bidirectional"))
    )
    (net (code "22") (name "/OTG") (class "Default")
      (node (ref "R7") (pin "2") (pinfunction "2_2") (pintype "passive"))
      (node (ref "U14") (pin "8") (pinfunction "OTG_8") (pintype "bidirectional"))
    )
    (net (code "23") (name "/PMIC_SYS") (class "Default")
      (node (ref "C47") (pin "1") (pinfunction "1_1") (pintype "passive"))
      (node (ref "C58") (pin "1") (pinfunction "1_1") (pintype "passive"))
      (node (ref "C59") (pin "1") (pinfunction "1_1") (pintype "passive"))
      (node (ref "L7") (pin "P$2") (pinfunction "2_P$2") (pintype "passive"))
      (node (ref "R4") (pin "2") (pinfunction "2_2") (pintype "passive"))
      (node (ref "R44") (pin "2") (pinfunction "2_2") (pintype "passive"))
      (node (ref "U14") (pin "15") (pinfunction "SYS_15") (pintype "power_in"))
      (node (ref "U14") (pin "16") (pinfunction "SYS_16") (pintype "power_in"))
      (node (ref "U2") (pin "5") (pinfunction "VIN_5") (pintype "power_in"))
    )
    (net (code "24") (name "/PMID") (class "Default")
      (node (ref "C56") (pin "1") (pinfunction "1_1") (pintype "passive"))
      (node (ref "C62") (pin "1") (pinfunction "1_1") (pintype "passive"))
      (node (ref "U14") (pin "23") (pinfunction "PMID_23") (pintype "passive"))
    )
    (net (code "25") (name "/PWR_ON_UB") (class "Default")
      (node (ref "R43") (pin "2") (pinfunction "2_2") (pintype "passive"))
      (node (ref "U5") (pin "15") (pinfunction "PWR_ON_15") (pintype "bidirectional"))
      (node (ref "U6") (pin "4") (pinfunction "B_4") (pintype "bidirectional"))
    )
    (net (code "26") (name "/REGN") (class "Default")
      (node (ref "C65") (pin "1") (pinfunction "1_1") (pintype "passive"))
      (node (ref "R35") (pin "1") (pinfunction "1_1") (pintype "passive"))
      (node (ref "U14") (pin "22") (pinfunction "REGN_22") (pintype "bidirectional"))
    )
    (net (code "27") (name "/SIM_CLK") (class "Default")
      (node (ref "U4") (pin "8") (pinfunction "CLK_8") (pintype "bidirectional"))
      (node (ref "U5") (pin "38") (pinfunction "SIM_CLK_38") (pintype "bidirectional"))
    )
    (net (code "28") (name "/SIM_IO") (class "Default")
      (node (ref "U4") (pin "12") (pinfunction "DATA_12") (pintype "bidirectional"))
      (node (ref "U5") (pin "39") (pinfunction "SIM_IO_39") (pintype "bidirectional"))
    )
    (net (code "29") (name "/SIM_RST") (class "Default")
      (node (ref "U4") (pin "4") (pinfunction "RST_4") (pintype "bidirectional"))
      (node (ref "U5") (pin "40") (pinfunction "SIM_RST_40") (pintype "bidirectional"))
    )
    (net (code "30") (name "/SIM_SELECT") (class "Default")
      (node (ref "R14") (pin "1") (pinfunction "1_1") (pintype "passive"))
      (node (ref "R15") (pin "2") (pinfunction "2_2") (pintype "passive"))
      (node (ref "U4") (pin "2") (pinfunction "SEL_2") (pintype "bidirectional"))
      (node (ref "U5") (pin "23") (pinfunction "GPIO2_23") (pintype "bidirectional"))
    )
    (net (code "31") (name "/SIM_VCC") (class "Default")
      (node (ref "U4") (pin "16") (pinfunction "VSIM_16") (pintype "bidirectional"))
      (node (ref "U5") (pin "41") (pinfunction "VSIM_41") (pintype "bidirectional"))
    )
    (net (code "32") (name "/STAT") (class "Default")
      (node (ref "D5") (pin "C") (pinfunction "C_C") (pintype "passive"))
      (node (ref "U14") (pin "4") (pinfunction "STAT_4") (pintype "bidirectional"))
    )
    (net (code "33") (name "/SW1") (class "Default")
      (node (ref "C17") (pin "2") (pinfunction "2_2") (pintype "passive"))
      (node (ref "L7") (pin "P$1") (pinfunction "1_P$1") (pintype "passive"))
      (node (ref "U14") (pin "19") (pinfunction "SW_19") (pintype "power_in"))
      (node (ref "U14") (pin "20") (pinfunction "SW_20") (pintype "power_in"))
    )
    (net (code "34") (name "/SYS_PWR_EN") (class "Default")
      (node (ref "CONN2") (pin "2") (pinfunction "2_2") (pintype "passive"))
      (node (ref "R4") (pin "1") (pinfunction "1_1") (pintype "passive"))
      (node (ref "U2") (pin "4") (pinfunction "CE_4") (pintype "bidirectional"))
    )
    (net (code "35") (name "/TS") (class "Default")
      (node (ref "R34") (pin "1") (pinfunction "1_1") (pintype "passive"))
      (node (ref "R35") (pin "2") (pinfunction "2_2") (pintype "passive"))
      (node (ref "U14") (pin "11") (pinfunction "TS_11") (pintype "bidirectional"))
      (node (ref "U14") (pin "12") (pinfunction "~{QON}_12") (pintype "bidirectional"))
    )
    (net (code "36") (name "/UBLOX_GPIO3") (class "Default")
      (node (ref "U5") (pin "24") (pinfunction "GPIO3_24") (pintype "bidirectional"))
    )
    (net (code "37") (name "/UBLOX_GPIO4") (class "Default")
      (node (ref "U5") (pin "25") (pinfunction "GPIO4_25") (pintype "bidirectional"))
    )
    (net (code "38") (name "/UBLOX_PWR_DETECT") (class "Default")
      (node (ref "R39") (pin "2") (pinfunction "2_2") (pintype "passive"))
      (node (ref "U10") (pin "P$A12") (pinfunction "P0.02/AIN0_P$A12") (pintype "bidirectional"))
      (node (ref "U8") (pin "4") (pinfunction "Y_4") (pintype "bidirectional"))
    )
    (net (code "39") (name "/UBLOX_SCL") (class "Default")
      (node (ref "U5") (pin "27") (pinfunction "SCL_27") (pintype "bidirectional"))
    )
    (net (code "40") (name "/UBLOX_SDA") (class "Default")
      (node (ref "U5") (pin "26") (pinfunction "SDA_26") (pintype "bidirectional"))
    )
    (net (code "41") (name "/UB_USB_DET") (class "Default")
      (node (ref "U$20") (pin "P$1") (pinfunction "TP_P$1") (pintype "bidirectional"))
      (node (ref "U5") (pin "17") (pinfunction "VUSB_DET_17") (pintype "bidirectional"))
    )
    (net (code "42") (name "/UB_USB_N") (class "Default")
      (node (ref "U$19") (pin "P$1") (pinfunction "TP_P$1") (pintype "bidirectional"))
      (node (ref "U5") (pin "28") (pinfunction "RXD_AUX/USB_D-_28") (pintype "bidirectional"))
    )
    (net (code "43") (name "/UB_USB_P") (class "Default")
      (node (ref "U$18") (pin "P$1") (pinfunction "TP_P$1") (pintype "bidirectional"))
      (node (ref "U5") (pin "29") (pinfunction "TXD_AUX/USB_D+_29") (pintype "bidirectional"))
    )
    (net (code "44") (name "/VBUS_NRF") (class "Default")
      (node (ref "C26") (pin "1") (pinfunction "1_1") (pintype "passive"))
      (node (ref "D4") (pin "ANODE") (pinfunction "ANODE_ANODE") (pintype "bidirectional"))
      (node (ref "U10") (pin "P$AD2") (pinfunction "VBUS_P$AD2") (pintype "power_in"))
      (node (ref "USB") (pin "1") (pinfunction "VBUS_1") (pintype "bidirectional"))
    )
    (net (code "45") (name "/VIN") (class "Default")
      (node (ref "C57") (pin "1") (pinfunction "1_1") (pintype "passive"))
      (node (ref "C60") (pin "1") (pinfunction "1_1") (pintype "passive"))
      (node (ref "C64") (pin "1") (pinfunction "1_1") (pintype "passive"))
      (node (ref "CONN2") (pin "3") (pinfunction "3_3") (pintype "passive"))
      (node (ref "D4") (pin "CATHODE") (pinfunction "CATHODE_CATHODE") (pintype "bidirectional"))
      (node (ref "U14") (pin "1") (pinfunction "VBUS_1") (pintype "power_in"))
      (node (ref "U14") (pin "24") (pinfunction "VBUS_24") (pintype "passive"))
    )
    (net (code "46") (name "/~{ANT_SELECT}") (class "Default")
      (node (ref "C41") (pin "1") (pinfunction "1_1") (pintype "passive"))
      (node (ref "U$7") (pin "P$4") (pinfunction "VCTL2_P$4") (pintype "bidirectional"))
      (node (ref "U11") (pin "4") (pinfunction "~{A}_4") (pintype "bidirectional"))
    )
    (net (code "47") (name "/~{CE}") (class "Default")
      (node (ref "R8") (pin "2") (pinfunction "2_2") (pintype "passive"))
      (node (ref "U14") (pin "9") (pinfunction "~{CE}_9") (pintype "output"))
    )
    (net (code "48") (name "/~{NRF_RESET}") (class "Default")
      (node (ref "C51") (pin "1") (pinfunction "1_1") (pintype "passive"))
      (node (ref "CONN4") (pin "10") (pinfunction "10_10") (pintype "bidirectional"))
      (node (ref "CONN6") (pin "16") (pinfunction "16_16") (pintype "passive"))
      (node (ref "R13") (pin "2") (pinfunction "2_2") (pintype "passive"))
      (node (ref "S2") (pin "3") (pinfunction "3_3") (pintype "passive"))
      (node (ref "S2") (pin "4") (pinfunction "4_4") (pintype "passive"))
      (node (ref "U10") (pin "P$AC13") (pinfunction "P0.18/RESET_P$AC13") (pintype "bidirectional"))
    )
    (net (code "49") (name "/~{P0.05{slash}BAT_INT}") (class "Default")
      (node (ref "R2") (pin "2") (pinfunction "2_2") (pintype "passive"))
      (node (ref "U10") (pin "P$K2") (pinfunction "P0.05/AIN3_P$K2") (pintype "bidirectional"))
      (node (ref "U13") (pin "5") (pinfunction "ALT_5") (pintype "bidirectional"))
      (node (ref "U14") (pin "7") (pinfunction "INT_7") (pintype "bidirectional"))
    )
    (net (code "50") (name "/~{RESET_UB_NRF}") (class "Default")
      (node (ref "R9") (pin "1") (pinfunction "1_1") (pintype "passive"))
      (node (ref "U10") (pin "P$U1") (pinfunction "P0.12_P$U1") (pintype "bidirectional"))
      (node (ref "U3") (pin "2") (pinfunction "A_2") (pintype "bidirectional"))
    )
    (net (code "51") (name "/~{RESET_UB}") (class "Default")
      (node (ref "U3") (pin "4") (pinfunction "B_4") (pintype "bidirectional"))
      (node (ref "U5") (pin "18") (pinfunction "RESET_N_18") (pintype "bidirectional"))
    )
    (net (code "52") (name "ANT_DET") (class "Default")
      (node (ref "U5") (pin "62") (pinfunction "ANT_DET_62") (pintype "bidirectional"))
    )
    (net (code "53") (name "ANT_SELECT") (class "Default")
      (node (ref "C36") (pin "1") (pinfunction "1_1") (pintype "passive"))
      (node (ref "R25") (pin "2") (pinfunction "2_2") (pintype "passive"))
      (node (ref "U$7") (pin "P$6") (pinfunction "VCTL1_P$6") (pintype "bidirectional"))
      (node (ref "U10") (pin "P$M2") (pinfunction "P0.07_P$M2") (pintype "bidirectional"))
      (node (ref "U11") (pin "2") (pinfunction "A_2") (pintype "bidirectional"))
    )
    (net (code "54") (name "BAT") (class "Default")
      (node (ref "C63") (pin "1") (pinfunction "1_1") (pintype "passive"))
      (node (ref "CONN2") (pin "1") (pinfunction "1_1") (pintype "passive"))
      (node (ref "J3") (pin "2") (pinfunction "1_2") (pintype "passive"))
      (node (ref "R29") (pin "2") (pinfunction "2_2") (pintype "passive"))
      (node (ref "U14") (pin "13") (pinfunction "BAT_13") (pintype "passive"))
      (node (ref "U14") (pin "14") (pinfunction "BAT_14") (pintype "power_in"))
    )
    (net (code "55") (name "CTS_UB") (class "Default")
      (node (ref "R21") (pin "2") (pinfunction "2_2") (pintype "passive"))
      (node (ref "U12") (pin "10") (pinfunction "B3_10") (pintype "bidirectional"))
      (node (ref "U5") (pin "11") (pinfunction "CTS_11") (pintype "bidirectional"))
    )
    (net (code "56") (name "DCD_UB") (class "Default")
      (node (ref "U5") (pin "8") (pinfunction "DCD_8") (pintype "bidirectional"))
    )
    (net (code "57") (name "DSR_UB") (class "Default")
      (node (ref "R38") (pin "1") (pinfunction "1_1") (pintype "passive"))
      (node (ref "U5") (pin "6") (pinfunction "DSR_6") (pintype "bidirectional"))
    )
    (net (code "58") (name "DTR_UB") (class "Default")
      (node (ref "U5") (pin "9") (pinfunction "DTR_9") (pintype "bidirectional"))
    )
    (net (code "59") (name "GND") (class "Default")
      (node (ref "C1") (pin "2") (pinfunction "2_2") (pintype "passive"))
      (node (ref "C10") (pin "2") (pinfunction "2_2") (pintype "passive"))
      (node (ref "C11") (pin "2") (pinfunction "2_2") (pintype "passive"))
      (node (ref "C12") (pin "2") (pinfunction "2_2") (pintype "passive"))
      (node (ref "C13") (pin "2") (pinfunction "2_2") (pintype "passive"))
      (node (ref "C14") (pin "2") (pinfunction "2_2") (pintype "passive"))
      (node (ref "C15") (pin "2") (pinfunction "2_2") (pintype "passive"))
      (node (ref "C16") (pin "2") (pinfunction "2_2") (pintype "passive"))
      (node (ref "C18") (pin "2") (pinfunction "2_2") (pintype "passive"))
      (node (ref "C19") (pin "2") (pinfunction "2_2") (pintype "passive"))
      (node (ref "C2") (pin "2") (pinfunction "2_2") (pintype "passive"))
      (node (ref "C20") (pin "2") (pinfunction "2_2") (pintype "passive"))
      (node (ref "C21") (pin "2") (pinfunction "2_2") (pintype "passive"))
      (node (ref "C22") (pin "2") (pinfunction "2_2") (pintype "passive"))
      (node (ref "C23") (pin "2") (pinfunction "2_2") (pintype "passive"))
      (node (ref "C24") (pin "2") (pinfunction "2_2") (pintype "passive"))
      (node (ref "C25") (pin "2") (pinfunction "2_2") (pintype "passive"))
      (node (ref "C26") (pin "2") (pinfunction "2_2") (pintype "passive"))
      (node (ref "C27") (pin "2") (pinfunction "2_2") (pintype "passive"))
      (node (ref "C28") (pin "2") (pinfunction "2_2") (pintype "passive"))
      (node (ref "C29") (pin "2") (pinfunction "2_2") (pintype "passive"))
      (node (ref "C3") (pin "2") (pinfunction "2_2") (pintype "passive"))
      (node (ref "C30") (pin "2") (pinfunction "2_2") (pintype "passive"))
      (node (ref "C31") (pin "2") (pinfunction "2_2") (pintype "passive"))
      (node (ref "C32") (pin "2") (pinfunction "2_2") (pintype "passive"))
      (node (ref "C33") (pin "2") (pinfunction "2_2") (pintype "passive"))
      (node (ref "C34") (pin "2") (pinfunction "2_2") (pintype "passive"))
      (node (ref "C35") (pin "2") (pinfunction "2_2") (pintype "passive"))
      (node (ref "C36") (pin "2") (pinfunction "2_2") (pintype "passive"))
      (node (ref "C38") (pin "2") (pinfunction "2_2") (pintype "passive"))
      (node (ref "C39") (pin "2") (pinfunction "2_2") (pintype "passive"))
      (node (ref "C4") (pin "2") (pinfunction "2_2") (pintype "passive"))
      (node (ref "C40") (pin "2") (pinfunction "2_2") (pintype "passive"))
      (node (ref "C41") (pin "2") (pinfunction "2_2") (pintype "passive"))
      (node (ref "C42") (pin "2") (pinfunction "2_2") (pintype "passive"))
      (node (ref "C43") (pin "2") (pinfunction "2_2") (pintype "passive"))
      (node (ref "C45") (pin "2") (pinfunction "2_2") (pintype "passive"))
      (node (ref "C46") (pin "2") (pinfunction "2_2") (pintype "passive"))
      (node (ref "C47") (pin "2") (pinfunction "2_2") (pintype "passive"))
      (node (ref "C48") (pin "2") (pinfunction "2_2") (pintype "passive"))
      (node (ref "C49") (pin "2") (pinfunction "2_2") (pintype "passive"))
      (node (ref "C5") (pin "2") (pinfunction "2_2") (pintype "passive"))
      (node (ref "C50") (pin "2") (pinfunction "2_2") (pintype "passive"))
      (node (ref "C51") (pin "2") (pinfunction "2_2") (pintype "passive"))
      (node (ref "C54") (pin "2") (pinfunction "2_2") (pintype "passive"))
      (node (ref "C55") (pin "2") (pinfunction "2_2") (pintype "passive"))
      (node (ref "C56") (pin "2") (pinfunction "2_2") (pintype "passive"))
      (node (ref "C57") (pin "2") (pinfunction "2_2") (pintype "passive"))
      (node (ref "C58") (pin "2") (pinfunction "2_2") (pintype "passive"))
      (node (ref "C59") (pin "2") (pinfunction "2_2") (pintype "passive"))
      (node (ref "C6") (pin "2") (pinfunction "2_2") (pintype "passive"))
      (node (ref "C60") (pin "2") (pinfunction "2_2") (pintype "passive"))
      (node (ref "C62") (pin "2") (pinfunction "2_2") (pintype "passive"))
      (node (ref "C63") (pin "2") (pinfunction "2_2") (pintype "passive"))
      (node (ref "C64") (pin "2") (pinfunction "2_2") (pintype "passive"))
      (node (ref "C65") (pin "2") (pinfunction "2_2") (pintype "passive"))
      (node (ref "C68") (pin "2") (pinfunction "2_2") (pintype "passive"))
      (node (ref "C7") (pin "2") (pinfunction "2_2") (pintype "passive"))
      (node (ref "C73") (pin "2") (pinfunction "2_2") (pintype "passive"))
      (node (ref "C74") (pin "2") (pinfunction "2_2") (pintype "passive"))
      (node (ref "C8") (pin "2") (pinfunction "2_2") (pintype "passive"))
      (node (ref "C9") (pin "2") (pinfunction "2_2") (pintype "passive"))
      (node (ref "CONN1") (pin "C5") (pinfunction "GND_C5") (pintype "passive"))
      (node (ref "CONN4") (pin "3") (pinfunction "3_3") (pintype "bidirectional"))
      (node (ref "CONN4") (pin "5") (pinfunction "5_5") (pintype "bidirectional"))
      (node (ref "CONN4") (pin "9") (pinfunction "9_9") (pintype "bidirectional"))
      (node (ref "CONN6") (pin "13") (pinfunction "13_13") (pintype "passive"))
      (node (ref "J3") (pin "1") (pinfunction "2_1") (pintype "passive"))
      (node (ref "L4") (pin "2") (pinfunction "2_2") (pintype "passive"))
      (node (ref "R15") (pin "1") (pinfunction "1_1") (pintype "passive"))
      (node (ref "R17") (pin "1") (pinfunction "1_1") (pintype "passive"))
      (node (ref "R18") (pin "1") (pinfunction "1_1") (pintype "passive"))
      (node (ref "R19") (pin "1") (pinfunction "1_1") (pintype "passive"))
      (node (ref "R21") (pin "1") (pinfunction "1_1") (pintype "passive"))
      (node (ref "R25") (pin "1") (pinfunction "1_1") (pintype "passive"))
      (node (ref "R26") (pin "1") (pinfunction "1_1") (pintype "passive"))
      (node (ref "R27") (pin "1") (pinfunction "1_1") (pintype "passive"))
      (node (ref "R33") (pin "2") (pinfunction "2_2") (pintype "passive"))
      (node (ref "R34") (pin "2") (pinfunction "2_2") (pintype "passive"))
      (node (ref "R37") (pin "1") (pinfunction "1_1") (pintype "passive"))
      (node (ref "R38") (pin "2") (pinfunction "2_2") (pintype "passive"))
      (node (ref "R39") (pin "1") (pinfunction "1_1") (pintype "passive"))
      (node (ref "R8") (pin "1") (pinfunction "1_1") (pintype "passive"))
      (node (ref "S1") (pin "1") (pinfunction "1_1") (pintype "passive"))
      (node (ref "S1") (pin "2") (pinfunction "2_2") (pintype "passive"))
      (node (ref "S2") (pin "1") (pinfunction "1_1") (pintype "passive"))
      (node (ref "S2") (pin "2") (pinfunction "2_2") (pintype "passive"))
      (node (ref "U$7") (pin "P$2") (pinfunction "GND_P$2") (pintype "bidirectional"))
      (node (ref "U$7") (pin "P$7") (pinfunction "GND_P$7") (pintype "bidirectional"))
      (node (ref "U$7") (pin "P$8") (pinfunction "GND_P$8") (pintype "bidirectional"))
      (node (ref "U1") (pin "2") (pinfunction "VSS_2") (pintype "power_in"))
      (node (ref "U1") (pin "5") (pinfunction "VSS_5") (pintype "power_in"))
      (node (ref "U1") (pin "P$1") (pinfunction "VSS_P$1") (pintype "power_in"))
      (node (ref "U10") (pin "P$74") (pinfunction "VSS_PAD_P$74") (pintype "bidirectional"))
      (node (ref "U10") (pin "P$75") (pinfunction "VSS_PAD_P$75") (pintype "bidirectional"))
      (node (ref "U10") (pin "P$76") (pinfunction "VSS_PAD_P$76") (pintype "bidirectional"))
      (node (ref "U10") (pin "P$77") (pinfunction "VSS_PAD_P$77") (pintype "bidirectional"))
      (node (ref "U10") (pin "P$78") (pinfunction "VSS_PAD_P$78") (pintype "bidirectional"))
      (node (ref "U10") (pin "P$79") (pinfunction "VSS_PAD_P$79") (pintype "bidirectional"))
      (node (ref "U10") (pin "P$80") (pinfunction "VSS_PAD_P$80") (pintype "bidirectional"))
      (node (ref "U10") (pin "P$81") (pinfunction "VSS_PAD_P$81") (pintype "bidirectional"))
      (node (ref "U10") (pin "P$82") (pinfunction "VSS_PAD_P$82") (pintype "bidirectional"))
      (node (ref "U10") (pin "P$83") (pinfunction "VSS_PAD_P$83") (pintype "bidirectional"))
      (node (ref "U10") (pin "P$B7") (pinfunction "VSS_P$B7") (pintype "power_in"))
      (node (ref "U10") (pin "P$F23") (pinfunction "VSS_PA_P$F23") (pintype "bidirectional"))
      (node (ref "U11") (pin "3") (pinfunction "GND_3") (pintype "power_in"))
      (node (ref "U12") (pin "5") (pinfunction "DIR3_5") (pintype "bidirectional"))
      (node (ref "U12") (pin "6") (pinfunction "DIR4_6") (pintype "bidirectional"))
      (node (ref "U12") (pin "7") (pinfunction "~{OE}_7") (pintype "bidirectional"))
      (node (ref "U12") (pin "8") (pinfunction "GND_8") (pintype "power_in"))
      (node (ref "U13") (pin "1") (pinfunction "CTG_1") (pintype "bidirectional"))
      (node (ref "U13") (pin "4") (pinfunction "GND_4") (pintype "bidirectional"))
      (node (ref "U13") (pin "6") (pinfunction "QST_6") (pintype "bidirectional"))
      (node (ref "U13") (pin "EP") (pinfunction "GND_EP") (pintype "bidirectional"))
      (node (ref "U14") (pin "17") (pinfunction "PGND_17") (pintype "passive"))
      (node (ref "U14") (pin "18") (pinfunction "PGND_18") (pintype "passive"))
      (node (ref "U14") (pin "PAD") (pinfunction "PAD_PAD") (pintype "power_in"))
      (node (ref "U14") (pin "PAD@1") (pinfunction "PAD_PAD@1") (pintype "power_in"))
      (node (ref "U14") (pin "PAD@2") (pinfunction "PAD_PAD@2") (pintype "power_in"))
      (node (ref "U14") (pin "PAD@3") (pinfunction "PAD_PAD@3") (pintype "power_in"))
      (node (ref "U14") (pin "PAD@4") (pinfunction "PAD_PAD@4") (pintype "power_in"))
      (node (ref "U14") (pin "PAD@5") (pinfunction "PAD_PAD@5") (pintype "power_in"))
      (node (ref "U14") (pin "PAD@6") (pinfunction "PAD_PAD@6") (pintype "power_in"))
      (node (ref "U14") (pin "PAD@7") (pinfunction "PAD_PAD@7") (pintype "power_in"))
      (node (ref "U14") (pin "PAD@8") (pinfunction "PAD_PAD@8") (pintype "power_in"))
      (node (ref "U14") (pin "PAD@9") (pinfunction "PAD_PAD@9") (pintype "power_in"))
      (node (ref "U15") (pin "2") (pinfunction "GND_2") (pintype "passive"))
      (node (ref "U2") (pin "2") (pinfunction "VSS_2") (pintype "power_in"))
      (node (ref "U3") (pin "3") (pinfunction "GND_3") (pintype "bidirectional"))
      (node (ref "U4") (pin "6") (pinfunction "GND_6") (pintype "power_in"))
      (node (ref "U5") (pin "1") (pinfunction "GND_1") (pintype "bidirectional"))
      (node (ref "U5") (pin "14") (pinfunction "GND_14") (pintype "bidirectional"))
      (node (ref "U5") (pin "20") (pinfunction "GND_20") (pintype "bidirectional"))
      (node (ref "U5") (pin "21") (pinfunction "GND_21") (pintype "bidirectional"))
      (node (ref "U5") (pin "22") (pinfunction "GND_22") (pintype "bidirectional"))
      (node (ref "U5") (pin "3") (pinfunction "GND_3") (pintype "bidirectional"))
      (node (ref "U5") (pin "30") (pinfunction "GND_30") (pintype "bidirectional"))
      (node (ref "U5") (pin "32") (pinfunction "GND_32") (pintype "bidirectional"))
      (node (ref "U5") (pin "43") (pinfunction "GND_43") (pintype "bidirectional"))
      (node (ref "U5") (pin "5") (pinfunction "GND_5") (pintype "bidirectional"))
      (node (ref "U5") (pin "50") (pinfunction "GND_50") (pintype "bidirectional"))
      (node (ref "U5") (pin "54") (pinfunction "GND_54") (pintype "bidirectional"))
      (node (ref "U5") (pin "55") (pinfunction "GND_55") (pintype "bidirectional"))
      (node (ref "U5") (pin "57") (pinfunction "GND_57") (pintype "bidirectional"))
      (node (ref "U5") (pin "58") (pinfunction "GND_58") (pintype "bidirectional"))
      (node (ref "U5") (pin "59") (pinfunction "GND_59") (pintype "bidirectional"))
      (node (ref "U5") (pin "60") (pinfunction "GND_60") (pintype "bidirectional"))
      (node (ref "U5") (pin "61") (pinfunction "GND_61") (pintype "bidirectional"))
      (node (ref "U5") (pin "63") (pinfunction "GND_63") (pintype "bidirectional"))
      (node (ref "U5") (pin "64") (pinfunction "GND_64") (pintype "bidirectional"))
      (node (ref "U5") (pin "65") (pinfunction "GND65...96_65") (pintype "bidirectional"))
      (node (ref "U5") (pin "66") (pinfunction "GND65...96_66") (pintype "bidirectional"))
      (node (ref "U5") (pin "67") (pinfunction "GND65...96_67") (pintype "bidirectional"))
      (node (ref "U5") (pin "68") (pinfunction "GND65...96_68") (pintype "bidirectional"))
      (node (ref "U5") (pin "69") (pinfunction "GND65...96_69") (pintype "bidirectional"))
      (node (ref "U5") (pin "70") (pinfunction "GND65...96_70") (pintype "bidirectional"))
      (node (ref "U5") (pin "71") (pinfunction "GND65...96_71") (pintype "bidirectional"))
      (node (ref "U5") (pin "72") (pinfunction "GND65...96_72") (pintype "bidirectional"))
      (node (ref "U5") (pin "73") (pinfunction "GND65...96_73") (pintype "bidirectional"))
      (node (ref "U5") (pin "74") (pinfunction "GND65...96_74") (pintype "bidirectional"))
      (node (ref "U5") (pin "75") (pinfunction "GND65...96_75") (pintype "bidirectional"))
      (node (ref "U5") (pin "76") (pinfunction "GND65...96_76") (pintype "bidirectional"))
      (node (ref "U5") (pin "77") (pinfunction "GND65...96_77") (pintype "bidirectional"))
      (node (ref "U5") (pin "78") (pinfunction "GND65...96_78") (pintype "bidirectional"))
      (node (ref "U5") (pin "79") (pinfunction "GND65...96_79") (pintype "bidirectional"))
      (node (ref "U5") (pin "80") (pinfunction "GND65...96_80") (pintype "bidirectional"))
      (node (ref "U5") (pin "81") (pinfunction "GND65...96_81") (pintype "bidirectional"))
      (node (ref "U5") (pin "82") (pinfunction "GND65...96_82") (pintype "bidirectional"))
      (node (ref "U5") (pin "83") (pinfunction "GND65...96_83") (pintype "bidirectional"))
      (node (ref "U5") (pin "84") (pinfunction "GND65...96_84") (pintype "bidirectional"))
      (node (ref "U5") (pin "85") (pinfunction "GND65...96_85") (pintype "bidirectional"))
      (node (ref "U5") (pin "86") (pinfunction "GND65...96_86") (pintype "bidirectional"))
      (node (ref "U5") (pin "87") (pinfunction "GND65...96_87") (pintype "bidirectional"))
      (node (ref "U5") (pin "88") (pinfunction "GND65...96_88") (pintype "bidirectional"))
      (node (ref "U5") (pin "89") (pinfunction "GND65...96_89") (pintype "bidirectional"))
      (node (ref "U5") (pin "90") (pinfunction "GND65...96_90") (pintype "bidirectional"))
      (node (ref "U5") (pin "91") (pinfunction "GND65...96_91") (pintype "bidirectional"))
      (node (ref "U5") (pin "92") (pinfunction "GND65...96_92") (pintype "bidirectional"))
      (node (ref "U5") (pin "93") (pinfunction "GND65...96_93") (pintype "bidirectional"))
      (node (ref "U5") (pin "94") (pinfunction "GND65...96_94") (pintype "bidirectional"))
      (node (ref "U5") (pin "95") (pinfunction "GND65...96_95") (pintype "bidirectional"))
      (node (ref "U5") (pin "96") (pinfunction "GND65...96_96") (pintype "bidirectional"))
      (node (ref "U6") (pin "3") (pinfunction "GND_3") (pintype "bidirectional"))
      (node (ref "U7") (pin "1") (pinfunction "GND_1") (pintype "power_in"))
      (node (ref "U7") (pin "2") (pinfunction "VPP_2") (pintype "power_in"))
      (node (ref "U7") (pin "4") (pinfunction "NA1_4") (pintype "bidirectional"))
      (node (ref "U7") (pin "5") (pinfunction "NA2_5") (pintype "bidirectional"))
      (node (ref "U8") (pin "3") (pinfunction "GND_3") (pintype "power_in"))
      (node (ref "U9") (pin "10") (pinfunction "GND1_10") (pintype "bidirectional"))
      (node (ref "U9") (pin "4") (pinfunction "GND_4") (pintype "bidirectional"))
      (node (ref "U9") (pin "9") (pinfunction "GND1_9") (pintype "bidirectional"))
      (node (ref "USB") (pin "5") (pinfunction "GND3_5") (pintype "bidirectional"))
      (node (ref "USB") (pin "6") (pinfunction "GND_6") (pintype "bidirectional"))
      (node (ref "USB") (pin "7") (pinfunction "GND1_7") (pintype "bidirectional"))
      (node (ref "USB") (pin "8") (pinfunction "GND4_8") (pintype "bidirectional"))
      (node (ref "USB") (pin "9") (pinfunction "GND5_9") (pintype "bidirectional"))
      (node (ref "X3") (pin "2@1") (pinfunction "GND_2@1") (pintype "passive"))
      (node (ref "X3") (pin "2@2") (pinfunction "GND_2@2") (pintype "passive"))
      (node (ref "X4") (pin "2@1") (pinfunction "GND_2@1") (pintype "passive"))
      (node (ref "X4") (pin "2@2") (pinfunction "GND_2@2") (pintype "passive"))
    )
    (net (code "60") (name "GPIO1_UB") (class "Default")
      (node (ref "R32") (pin "2") (pinfunction "2_2") (pintype "passive"))
      (node (ref "U5") (pin "16") (pinfunction "GPIO1_16") (pintype "bidirectional"))
    )
    (net (code "61") (name "Net-(ANT1-SIGNAL)") (class "Default")
      (node (ref "ANT1") (pin "1") (pinfunction "SIGNAL_1") (pintype "bidirectional"))
      (node (ref "C72") (pin "2") (pinfunction "2_2") (pintype "passive"))
      (node (ref "C74") (pin "1") (pinfunction "1_1") (pintype "passive"))
    )
    (net (code "62") (name "Net-(C37-Pad2)") (class "Default")
      (node (ref "C37") (pin "2") (pinfunction "2_2") (pintype "passive"))
      (node (ref "L4") (pin "1") (pinfunction "1_1") (pintype "passive"))
      (node (ref "X3") (pin "1") (pinfunction "1_1") (pintype "passive"))
    )
    (net (code "63") (name "Net-(C70-Pad2)") (class "Default")
      (node (ref "C70") (pin "2") (pinfunction "2_2") (pintype "passive"))
      (node (ref "X4") (pin "1") (pinfunction "1_1") (pintype "passive"))
    )
    (net (code "64") (name "Net-(C71-Pad2)") (class "Default")
      (node (ref "C71") (pin "2") (pinfunction "2_2") (pintype "passive"))
      (node (ref "C72") (pin "1") (pinfunction "1_1") (pintype "passive"))
      (node (ref "C73") (pin "1") (pinfunction "1_1") (pintype "passive"))
    )
    (net (code "65") (name "Net-(D3-PadC)") (class "Default")
      (node (ref "D3") (pin "C") (pinfunction "C_C") (pintype "passive"))
      (node (ref "R19") (pin "2") (pinfunction "2_2") (pintype "passive"))
    )
    (net (code "66") (name "Net-(D5-PadA)") (class "Default")
      (node (ref "D5") (pin "A") (pinfunction "A_A") (pintype "passive"))
      (node (ref "R44") (pin "1") (pinfunction "1_1") (pintype "passive"))
    )
    (net (code "67") (name "Net-(L1-1)") (class "Default")
      (node (ref "L1") (pin "P$1") (pinfunction "1_P$1") (pintype "passive"))
      (node (ref "U1") (pin "1") (pinfunction "LX_1") (pintype "bidirectional"))
    )
    (net (code "68") (name "Net-(L2-Pad2)") (class "Default")
      (node (ref "L2") (pin "2") (pinfunction "2_2") (pintype "passive"))
      (node (ref "L3") (pin "1") (pinfunction "1_1") (pintype "passive"))
    )
    (net (code "69") (name "Net-(R20-Pad1)") (class "Default")
      (node (ref "R20") (pin "1") (pinfunction "1_1") (pintype "passive"))
      (node (ref "U5") (pin "51") (pinfunction "VCC_51") (pintype "bidirectional"))
      (node (ref "U5") (pin "52") (pinfunction "VCC_52") (pintype "bidirectional"))
      (node (ref "U5") (pin "53") (pinfunction "VCC_53") (pintype "bidirectional"))
    )
    (net (code "70") (name "Net-(R43-Pad1)") (class "Default")
      (node (ref "R43") (pin "1") (pinfunction "1_1") (pintype "passive"))
      (node (ref "U5") (pin "2") (pinfunction "RSVD_2") (pintype "bidirectional"))
    )
    (net (code "71") (name "Net-(U$6-2)") (class "Default")
      (node (ref "R12") (pin "2") (pinfunction "2_2") (pintype "passive"))
      (node (ref "U$6") (pin "BLUE") (pinfunction "2_BLUE") (pintype "passive"))
    )
    (net (code "72") (name "Net-(U$6-3)") (class "Default")
      (node (ref "R11") (pin "2") (pinfunction "2_2") (pintype "passive"))
      (node (ref "U$6") (pin "GREEN") (pinfunction "3_GREEN") (pintype "passive"))
    )
    (net (code "73") (name "Net-(U$6-4)") (class "Default")
      (node (ref "R10") (pin "2") (pinfunction "2_2") (pintype "passive"))
      (node (ref "U$6") (pin "RED") (pinfunction "4_RED") (pintype "passive"))
    )
    (net (code "74") (name "Net-(U$7-INPUT)") (class "Default")
      (node (ref "C44") (pin "1") (pinfunction "1_1") (pintype "passive"))
      (node (ref "U$7") (pin "P$5") (pinfunction "INPUT_P$5") (pintype "bidirectional"))
    )
    (net (code "75") (name "Net-(U$7-OUT1)") (class "Default")
      (node (ref "C70") (pin "1") (pinfunction "1_1") (pintype "passive"))
      (node (ref "U$7") (pin "P$1") (pinfunction "OUT1_P$1") (pintype "bidirectional"))
    )
    (net (code "76") (name "Net-(U$7-OUT2)") (class "Default")
      (node (ref "C71") (pin "1") (pinfunction "1_1") (pintype "passive"))
      (node (ref "U$7") (pin "P$3") (pinfunction "OUT2_P$3") (pintype "bidirectional"))
    )
    (net (code "77") (name "Net-(U1-CE)") (class "Default")
      (node (ref "R1") (pin "2") (pinfunction "2_2") (pintype "passive"))
      (node (ref "U1") (pin "4") (pinfunction "CE_4") (pintype "bidirectional"))
    )
    (net (code "78") (name "Net-(U8-A)") (class "Default")
      (node (ref "R31") (pin "1") (pinfunction "1_1") (pintype "passive"))
      (node (ref "R32") (pin "1") (pinfunction "1_1") (pintype "passive"))
      (node (ref "R37") (pin "2") (pinfunction "2_2") (pintype "passive"))
      (node (ref "U8") (pin "2") (pinfunction "A_2") (pintype "bidirectional"))
    )
    (net (code "79") (name "Net-(U10-ANT)") (class "Default")
      (node (ref "C40") (pin "1") (pinfunction "1_1") (pintype "passive"))
      (node (ref "L5") (pin "1") (pinfunction "1_1") (pintype "passive"))
      (node (ref "U10") (pin "P$H23") (pinfunction "ANT_P$H23") (pintype "bidirectional"))
    )
    (net (code "80") (name "Net-(U10-D+)") (class "Default")
      (node (ref "R5") (pin "2") (pinfunction "2_2") (pintype "passive"))
      (node (ref "U10") (pin "P$AD6") (pinfunction "D+_P$AD6") (pintype "bidirectional"))
    )
    (net (code "81") (name "Net-(U10-D-)") (class "Default")
      (node (ref "R6") (pin "2") (pinfunction "2_2") (pintype "passive"))
      (node (ref "U10") (pin "P$AD4") (pinfunction "D-_P$AD4") (pintype "bidirectional"))
    )
    (net (code "82") (name "Net-(U10-DCC)") (class "Default")
      (node (ref "L2") (pin "1") (pinfunction "1_1") (pintype "passive"))
      (node (ref "U10") (pin "P$B3") (pinfunction "DCC_P$B3") (pintype "output"))
    )
    (net (code "83") (name "Net-(U10-DEC1)") (class "Default")
      (node (ref "C10") (pin "1") (pinfunction "1_1") (pintype "passive"))
      (node (ref "U10") (pin "P$C1") (pinfunction "DEC1_P$C1") (pintype "power_in"))
    )
    (net (code "84") (name "Net-(U10-DEC2)") (class "Default")
      (node (ref "C31") (pin "1") (pinfunction "1_1") (pintype "passive"))
      (node (ref "U10") (pin "P$A18") (pinfunction "DEC2_P$A18") (pintype "bidirectional"))
    )
    (net (code "85") (name "Net-(U10-P0.00{slash}XL1)") (class "Default")
      (node (ref "C29") (pin "1") (pinfunction "1_1") (pintype "passive"))
      (node (ref "U10") (pin "P$D2") (pinfunction "P0.00/XL1_P$D2") (pintype "bidirectional"))
      (node (ref "XT1") (pin "2") (pinfunction "2_2") (pintype "passive"))
    )
    (net (code "86") (name "Net-(U10-P0.01{slash}XL2)") (class "Default")
      (node (ref "C42") (pin "1") (pinfunction "1_1") (pintype "passive"))
      (node (ref "U10") (pin "P$F2") (pinfunction "P0.01/XL2_P$F2") (pintype "bidirectional"))
      (node (ref "XT1") (pin "1") (pinfunction "1_1") (pintype "passive"))
    )
    (net (code "87") (name "Net-(U10-XC1)") (class "Default")
      (node (ref "C46") (pin "1") (pinfunction "1_1") (pintype "passive"))
      (node (ref "U10") (pin "P$B24") (pinfunction "XC1_P$B24") (pintype "input"))
      (node (ref "XT2") (pin "1") (pinfunction "1_1") (pintype "passive"))
    )
    (net (code "88") (name "Net-(U10-XC2)") (class "Default")
      (node (ref "C45") (pin "1") (pinfunction "1_1") (pintype "passive"))
      (node (ref "U10") (pin "P$A23") (pinfunction "XC2_P$A23") (pintype "output"))
      (node (ref "XT2") (pin "3") (pinfunction "3_3") (pintype "passive"))
    )
    (net (code "89") (name "Net-(U12-DIR1)") (class "Default")
      (node (ref "C38") (pin "1") (pinfunction "1_1") (pintype "passive"))
      (node (ref "U12") (pin "14") (pinfunction "VCCA_14") (pintype "power_in"))
      (node (ref "U12") (pin "15") (pinfunction "DIR1_15") (pintype "bidirectional"))
      (node (ref "U12") (pin "16") (pinfunction "DIR2_16") (pintype "bidirectional"))
      (node (ref "U15") (pin "1") (pinfunction "VOUT_1") (pintype "output"))
    )
    (net (code "90") (name "Net-(U13-CELL)") (class "Default")
      (node (ref "C55") (pin "1") (pinfunction "1_1") (pintype "passive"))
      (node (ref "R29") (pin "1") (pinfunction "1_1") (pintype "passive"))
      (node (ref "U13") (pin "2") (pinfunction "CELL_2") (pintype "bidirectional"))
    )
    (net (code "91") (name "Net-(U13-VDD)") (class "Default")
      (node (ref "C54") (pin "1") (pinfunction "1_1") (pintype "passive"))
      (node (ref "R28") (pin "1") (pinfunction "1_1") (pintype "passive"))
      (node (ref "U13") (pin "3") (pinfunction "VDD_3") (pintype "bidirectional"))
    )
    (net (code "92") (name "P0.03{slash}A0") (class "Default")
      (node (ref "CONN6") (pin "12") (pinfunction "12_12") (pintype "passive"))
      (node (ref "U10") (pin "P$B13") (pinfunction "P0.03/AIN1_P$B13") (pintype "bidirectional"))
    )
    (net (code "93") (name "P0.04{slash}A1") (class "Default")
      (node (ref "CONN6") (pin "11") (pinfunction "11_11") (pintype "passive"))
      (node (ref "U10") (pin "P$J1") (pinfunction "P0.04/AIN2_P$J1") (pintype "bidirectional"))
    )
    (net (code "94") (name "P0.06{slash}TX") (class "Default")
      (node (ref "CONN6") (pin "2") (pinfunction "2_2") (pintype "passive"))
      (node (ref "U10") (pin "P$L1") (pinfunction "P0.06_P$L1") (pintype "bidirectional"))
    )
    (net (code "95") (name "P0.08{slash}RX") (class "Default")
      (node (ref "CONN6") (pin "3") (pinfunction "3_3") (pintype "passive"))
      (node (ref "U10") (pin "P$N1") (pinfunction "P0.08_P$N1") (pintype "bidirectional"))
    )
    (net (code "96") (name "P0.11{slash}MODE") (class "Default")
      (node (ref "CONN6") (pin "14") (pinfunction "14_14") (pintype "passive"))
      (node (ref "S1") (pin "3") (pinfunction "3_3") (pintype "passive"))
      (node (ref "S1") (pin "4") (pinfunction "4_4") (pintype "passive"))
      (node (ref "U10") (pin "P$T2") (pinfunction "P0.11_P$T2") (pintype "bidirectional"))
    )
    (net (code "97") (name "P0.17{slash}QSPI_CS") (class "Default")
      (node (ref "R24") (pin "2") (pinfunction "2_2") (pintype "passive"))
      (node (ref "U10") (pin "P$AD12") (pinfunction "P0.17_P$AD12") (pintype "bidirectional"))
      (node (ref "U9") (pin "1") (pinfunction "/CS_1") (pintype "bidirectional"))
    )
    (net (code "98") (name "P0.19{slash}QSPI_CLK") (class "Default")
      (node (ref "U10") (pin "P$AC15") (pinfunction "P0.19_P$AC15") (pintype "bidirectional"))
      (node (ref "U9") (pin "6") (pinfunction "CLK_6") (pintype "bidirectional"))
    )
    (net (code "99") (name "P0.20{slash}QSPI_MOSI") (class "Default")
      (node (ref "U10") (pin "P$AD16") (pinfunction "P0.20_P$AD16") (pintype "bidirectional"))
      (node (ref "U9") (pin "5") (pinfunction "SI_5") (pintype "bidirectional"))
    )
    (net (code "100") (name "P0.21{slash}QSPI_MISO") (class "Default")
      (node (ref "U10") (pin "P$AC17") (pinfunction "P0.21_P$AC17") (pintype "bidirectional"))
      (node (ref "U9") (pin "2") (pinfunction "SO_2") (pintype "bidirectional"))
    )
    (net (code "101") (name "P0.22{slash}QSPI_WP") (class "Default")
      (node (ref "R23") (pin "2") (pinfunction "2_2") (pintype "passive"))
      (node (ref "U10") (pin "P$AD18") (pinfunction "P0.22_P$AD18") (pintype "bidirectional"))
      (node (ref "U9") (pin "3") (pinfunction "/WP_3") (pintype "bidirectional"))
    )
    (net (code "102") (name "P0.23{slash}QSPI_HOLD") (class "Default")
      (node (ref "R22") (pin "2") (pinfunction "2_2") (pintype "passive"))
      (node (ref "U10") (pin "P$AC19") (pinfunction "P0.23_P$AC19") (pintype "bidirectional"))
      (node (ref "U9") (pin "7") (pinfunction "/HOLD_7") (pintype "bidirectional"))
    )
    (net (code "103") (name "P0.24{slash}SDA") (class "Default")
      (node (ref "R36") (pin "2") (pinfunction "2_2") (pintype "passive"))
      (node (ref "U10") (pin "P$AD20") (pinfunction "P0.24_P$AD20") (pintype "bidirectional"))
      (node (ref "U13") (pin "8") (pinfunction "SDA_8") (pintype "bidirectional"))
      (node (ref "U14") (pin "6") (pinfunction "SDA_6") (pintype "bidirectional"))
    )
    (net (code "104") (name "P0.25{slash}BUFF_PWR") (class "Default")
      (node (ref "U10") (pin "P$AC21") (pinfunction "P0.25_P$AC21") (pintype "bidirectional"))
      (node (ref "U15") (pin "4") (pinfunction "ON_4") (pintype "input"))
    )
    (net (code "105") (name "P0.26{slash}SDA") (class "Default")
      (node (ref "CONN2") (pin "12") (pinfunction "12_12") (pintype "passive"))
      (node (ref "U10") (pin "P$G1") (pinfunction "P0.26_P$G1") (pintype "bidirectional"))
    )
    (net (code "106") (name "P0.27{slash}SCL") (class "Default")
      (node (ref "CONN2") (pin "11") (pinfunction "11_11") (pintype "passive"))
      (node (ref "U10") (pin "P$H2") (pinfunction "P0.27_P$H2") (pintype "bidirectional"))
    )
    (net (code "107") (name "P0.28{slash}A2") (class "Default")
      (node (ref "CONN6") (pin "10") (pinfunction "10_10") (pintype "passive"))
      (node (ref "U10") (pin "P$B11") (pinfunction "P0.28/AIN4_P$B11") (pintype "bidirectional"))
    )
    (net (code "108") (name "P0.29{slash}A3") (class "Default")
      (node (ref "CONN6") (pin "9") (pinfunction "9_9") (pintype "passive"))
      (node (ref "U10") (pin "P$A10") (pinfunction "P0.29/AIN5_P$A10") (pintype "bidirectional"))
    )
    (net (code "109") (name "P0.30{slash}A4") (class "Default")
      (node (ref "CONN6") (pin "8") (pinfunction "8_8") (pintype "passive"))
      (node (ref "U10") (pin "P$B9") (pinfunction "P0.30/AIN6_P$B9") (pintype "bidirectional"))
    )
    (net (code "110") (name "P0.31{slash}A5") (class "Default")
      (node (ref "CONN6") (pin "7") (pinfunction "7_7") (pintype "passive"))
      (node (ref "U10") (pin "P$A8") (pinfunction "P0.31/AIN7_P$A8") (pintype "bidirectional"))
    )
    (net (code "111") (name "P1.01{slash}0") (class "Default")
      (node (ref "CONN2") (pin "10") (pinfunction "10_10") (pintype "passive"))
      (node (ref "U10") (pin "P$Y23") (pinfunction "P1.01_P$Y23") (pintype "bidirectional"))
    )
    (net (code "112") (name "P1.02{slash}1") (class "Default")
      (node (ref "CONN2") (pin "9") (pinfunction "9_9") (pintype "passive"))
      (node (ref "U10") (pin "P$W24") (pinfunction "P1.02_P$W24") (pintype "bidirectional"))
    )
    (net (code "113") (name "P1.03{slash}6") (class "Default")
      (node (ref "CONN2") (pin "4") (pinfunction "4_4") (pintype "passive"))
      (node (ref "U10") (pin "P$V23") (pinfunction "P1.03_P$V23") (pintype "bidirectional"))
    )
    (net (code "114") (name "P1.04{slash}RXD_UB_NRF") (class "Default")
      (node (ref "U10") (pin "P$U24") (pinfunction "P1.04_P$U24") (pintype "bidirectional"))
      (node (ref "U12") (pin "4") (pinfunction "A4_4") (pintype "bidirectional"))
    )
    (net (code "115") (name "P1.05{slash}TXD_UB_NRF") (class "Default")
      (node (ref "R26") (pin "2") (pinfunction "2_2") (pintype "passive"))
      (node (ref "U10") (pin "P$T23") (pinfunction "P1.05_P$T23") (pintype "bidirectional"))
      (node (ref "U12") (pin "2") (pinfunction "A2_2") (pintype "bidirectional"))
    )
    (net (code "116") (name "P1.06{slash}CTS_UB_NRF") (class "Default")
      (node (ref "U10") (pin "P$R24") (pinfunction "P1.06_P$R24") (pintype "bidirectional"))
      (node (ref "U12") (pin "3") (pinfunction "A3_3") (pintype "bidirectional"))
    )
    (net (code "117") (name "P1.07{slash}RTS_UB_NRF") (class "Default")
      (node (ref "R27") (pin "2") (pinfunction "2_2") (pintype "passive"))
      (node (ref "U10") (pin "P$P23") (pinfunction "P1.07_P$P23") (pintype "bidirectional"))
      (node (ref "U12") (pin "1") (pinfunction "A1_1") (pintype "bidirectional"))
    )
    (net (code "118") (name "P1.08{slash}2") (class "Default")
      (node (ref "CONN2") (pin "8") (pinfunction "8_8") (pintype "passive"))
      (node (ref "U10") (pin "P$P2") (pinfunction "P1.08_P$P2") (pintype "bidirectional"))
    )
    (net (code "119") (name "P1.09{slash}SCL") (class "Default")
      (node (ref "R30") (pin "2") (pinfunction "2_2") (pintype "passive"))
      (node (ref "U10") (pin "P$R1") (pinfunction "P1.09_P$R1") (pintype "bidirectional"))
      (node (ref "U13") (pin "7") (pinfunction "SCL_7") (pintype "bidirectional"))
      (node (ref "U14") (pin "5") (pinfunction "SCL_5") (pintype "output"))
    )
    (net (code "120") (name "P1.10{slash}3") (class "Default")
      (node (ref "CONN2") (pin "7") (pinfunction "7_7") (pintype "passive"))
      (node (ref "U10") (pin "P$A20") (pinfunction "P1.10_P$A20") (pintype "bidirectional"))
    )
    (net (code "121") (name "P1.11{slash}4") (class "Default")
      (node (ref "CONN2") (pin "6") (pinfunction "6_6") (pintype "passive"))
      (node (ref "U10") (pin "P$B19") (pinfunction "P1.11_P$B19") (pintype "bidirectional"))
    )
    (net (code "122") (name "P1.12{slash}5") (class "Default")
      (node (ref "CONN2") (pin "5") (pinfunction "5_5") (pintype "passive"))
      (node (ref "D3") (pin "A") (pinfunction "A_A") (pintype "passive"))
      (node (ref "U10") (pin "P$B17") (pinfunction "P1.12_P$B17") (pintype "bidirectional"))
    )
    (net (code "123") (name "P1.13{slash}MOSI") (class "Default")
      (node (ref "CONN6") (pin "5") (pinfunction "5_5") (pintype "passive"))
      (node (ref "U10") (pin "P$A16") (pinfunction "P1.13_P$A16") (pintype "bidirectional"))
    )
    (net (code "124") (name "P1.14{slash}MISO") (class "Default")
      (node (ref "CONN6") (pin "4") (pinfunction "4_4") (pintype "passive"))
      (node (ref "U10") (pin "P$B15") (pinfunction "P1.14_P$B15") (pintype "bidirectional"))
    )
    (net (code "125") (name "P1.15{slash}SCK") (class "Default")
      (node (ref "CONN6") (pin "6") (pinfunction "6_6") (pintype "passive"))
      (node (ref "U10") (pin "P$A14") (pinfunction "P1.15_P$A14") (pintype "bidirectional"))
    )
    (net (code "126") (name "PWR_ON_UB_NRF") (class "Default")
      (node (ref "R16") (pin "1") (pinfunction "1_1") (pintype "passive"))
      (node (ref "R17") (pin "2") (pinfunction "2_2") (pintype "passive"))
      (node (ref "U10") (pin "P$AC11") (pinfunction "P0.16_P$AC11") (pintype "bidirectional"))
      (node (ref "U6") (pin "2") (pinfunction "A_2") (pintype "bidirectional"))
    )
    (net (code "127") (name "RGB_BLUE") (class "Default")
      (node (ref "R12") (pin "1") (pinfunction "1_1") (pintype "passive"))
      (node (ref "U$11") (pin "P$1") (pinfunction "TP_P$1") (pintype "bidirectional"))
      (node (ref "U10") (pin "P$AD10") (pinfunction "P0.15_P$AD10") (pintype "bidirectional"))
    )
    (net (code "128") (name "RGB_GREEN") (class "Default")
      (node (ref "R11") (pin "1") (pinfunction "1_1") (pintype "passive"))
      (node (ref "U$10") (pin "P$1") (pinfunction "TP_P$1") (pintype "bidirectional"))
      (node (ref "U10") (pin "P$AC9") (pinfunction "P0.14_P$AC9") (pintype "bidirectional"))
    )
    (net (code "129") (name "RGB_RED") (class "Default")
      (node (ref "R10") (pin "1") (pinfunction "1_1") (pintype "passive"))
      (node (ref "U$9") (pin "P$1") (pinfunction "TP_P$1") (pintype "bidirectional"))
      (node (ref "U10") (pin "P$AD8") (pinfunction "P0.13_P$AD8") (pintype "bidirectional"))
    )
    (net (code "130") (name "RI_UB") (class "Default")
      (node (ref "U5") (pin "7") (pinfunction "RI_7") (pintype "bidirectional"))
    )
    (net (code "131") (name "RTS_UB") (class "Default")
      (node (ref "U12") (pin "12") (pinfunction "B1_12") (pintype "bidirectional"))
      (node (ref "U5") (pin "10") (pinfunction "RTS_10") (pintype "bidirectional"))
    )
    (net (code "132") (name "RXD_UB") (class "Default")
      (node (ref "R18") (pin "2") (pinfunction "2_2") (pintype "passive"))
      (node (ref "U12") (pin "9") (pinfunction "B4_9") (pintype "bidirectional"))
      (node (ref "U5") (pin "13") (pinfunction "RXD_13") (pintype "bidirectional"))
    )
    (net (code "133") (name "SWDCLK") (class "Default")
      (node (ref "CONN4") (pin "4") (pinfunction "4_4") (pintype "bidirectional"))
      (node (ref "U$4") (pin "P$1") (pinfunction "TP_P$1") (pintype "bidirectional"))
      (node (ref "U10") (pin "P$AA24") (pinfunction "SWDCLK_P$AA24") (pintype "input"))
    )
    (net (code "134") (name "SWDIO") (class "Default")
      (node (ref "CONN4") (pin "2") (pinfunction "2_2") (pintype "bidirectional"))
      (node (ref "U$1") (pin "P$1") (pinfunction "TP_P$1") (pintype "bidirectional"))
      (node (ref "U10") (pin "P$AC24") (pinfunction "SWDIO_P$AC24") (pintype "bidirectional"))
    )
    (net (code "135") (name "SWO") (class "Default")
      (node (ref "CONN4") (pin "6") (pinfunction "6_6") (pintype "bidirectional"))
      (node (ref "U$5") (pin "P$1") (pinfunction "TP_P$1") (pintype "bidirectional"))
      (node (ref "U10") (pin "P$AD22") (pinfunction "P1.00_P$AD22") (pintype "bidirectional"))
    )
    (net (code "136") (name "TXD_UB") (class "Default")
      (node (ref "U12") (pin "11") (pinfunction "B2_11") (pintype "bidirectional"))
      (node (ref "U5") (pin "12") (pinfunction "TXD_12") (pintype "bidirectional"))
    )
    (net (code "137") (name "VSYS") (class "Default")
      (node (ref "C19") (pin "1") (pinfunction "1_1") (pintype "passive"))
      (node (ref "C2") (pin "1") (pinfunction "1_1") (pintype "passive"))
      (node (ref "C20") (pin "1") (pinfunction "1_1") (pintype "passive"))
      (node (ref "C21") (pin "1") (pinfunction "1_1") (pintype "passive"))
      (node (ref "C22") (pin "1") (pinfunction "1_1") (pintype "passive"))
      (node (ref "C3") (pin "1") (pinfunction "1_1") (pintype "passive"))
      (node (ref "C35") (pin "1") (pinfunction "1_1") (pintype "passive"))
      (node (ref "R1") (pin "1") (pinfunction "1_1") (pintype "passive"))
      (node (ref "R20") (pin "2") (pinfunction "2_2") (pintype "passive"))
      (node (ref "U1") (pin "6") (pinfunction "VIN_6") (pintype "power_in"))
      (node (ref "U2") (pin "1") (pinfunction "VOUT_1") (pintype "power_in"))
    )
    (net (code "138") (name "V_INT") (class "Default")
      (node (ref "C39") (pin "1") (pinfunction "1_1") (pintype "passive"))
      (node (ref "C43") (pin "1") (pinfunction "1_1") (pintype "passive"))
      (node (ref "R14") (pin "2") (pinfunction "2_2") (pintype "passive"))
      (node (ref "R31") (pin "2") (pinfunction "2_2") (pintype "passive"))
      (node (ref "U12") (pin "13") (pinfunction "VCCB_13") (pintype "power_in"))
      (node (ref "U4") (pin "14") (pinfunction "VCC_14") (pintype "power_in"))
      (node (ref "U5") (pin "4") (pinfunction "V_INT_4") (pintype "bidirectional"))
    )
    (net (code "139") (name "unconnected-(CONN1-VPP-PadC6)") (class "Default")
      (node (ref "CONN1") (pin "C6") (pinfunction "VPP_C6") (pintype "passive"))
    )
    (net (code "140") (name "unconnected-(CONN4-Pad7)") (class "Default")
      (node (ref "CONN4") (pin "7") (pinfunction "7_7") (pintype "bidirectional"))
    )
    (net (code "141") (name "unconnected-(CONN4-Pad8)") (class "Default")
      (node (ref "CONN4") (pin "8") (pinfunction "8_8") (pintype "bidirectional"))
    )
    (net (code "142") (name "unconnected-(CONN6-Pad1)") (class "Default")
      (node (ref "CONN6") (pin "1") (pinfunction "1_1") (pintype "passive"))
    )
    (net (code "143") (name "unconnected-(U2-FLG-Pad3)") (class "Default")
      (node (ref "U2") (pin "3") (pinfunction "FLG_3") (pintype "bidirectional"))
    )
    (net (code "144") (name "unconnected-(U4-NC-Pad10)") (class "Default")
      (node (ref "U4") (pin "10") (pinfunction "NC_10") (pintype "no_connect"))
    )
    (net (code "145") (name "unconnected-(U5-GPIO6-Pad19)") (class "Default")
      (node (ref "U5") (pin "19") (pinfunction "GPIO6_19") (pintype "bidirectional"))
    )
    (net (code "146") (name "unconnected-(U5-RSVD-Pad31)") (class "Default")
      (node (ref "U5") (pin "31") (pinfunction "RSVD_31") (pintype "bidirectional"))
    )
    (net (code "147") (name "unconnected-(U5-RSVD-Pad33)") (class "Default")
      (node (ref "U5") (pin "33") (pinfunction "RSVD_33") (pintype "bidirectional"))
    )
    (net (code "148") (name "unconnected-(U5-RSVD-Pad34)") (class "Default")
      (node (ref "U5") (pin "34") (pinfunction "RSVD_34") (pintype "bidirectional"))
    )
    (net (code "149") (name "unconnected-(U5-RSVD-Pad35)") (class "Default")
      (node (ref "U5") (pin "35") (pinfunction "RSVD_35") (pintype "bidirectional"))
    )
    (net (code "150") (name "unconnected-(U5-RSVD-Pad36)") (class "Default")
      (node (ref "U5") (pin "36") (pinfunction "RSVD_36") (pintype "bidirectional"))
    )
    (net (code "151") (name "unconnected-(U5-RSVD-Pad37)") (class "Default")
      (node (ref "U5") (pin "37") (pinfunction "RSVD_37") (pintype "bidirectional"))
    )
    (net (code "152") (name "unconnected-(U5-SDIO_CLK-Pad45)") (class "Default")
      (node (ref "U5") (pin "45") (pinfunction "SDIO_CLK_45") (pintype "bidirectional"))
    )
    (net (code "153") (name "unconnected-(U5-SDIO_CMD-Pad46)") (class "Default")
      (node (ref "U5") (pin "46") (pinfunction "SDIO_CMD_46") (pintype "bidirectional"))
    )
    (net (code "154") (name "unconnected-(U5-SDIO_D0-Pad47)") (class "Default")
      (node (ref "U5") (pin "47") (pinfunction "SDIO_D0_47") (pintype "bidirectional"))
    )
    (net (code "155") (name "unconnected-(U5-SDIO_D1-Pad49)") (class "Default")
      (node (ref "U5") (pin "49") (pinfunction "SDIO_D1_49") (pintype "bidirectional"))
    )
    (net (code "156") (name "unconnected-(U5-SDIO_D2-Pad44)") (class "Default")
      (node (ref "U5") (pin "44") (pinfunction "SDIO_D2_44") (pintype "bidirectional"))
    )
    (net (code "157") (name "unconnected-(U5-SDIO_D3-Pad48)") (class "Default")
      (node (ref "U5") (pin "48") (pinfunction "SDIO_D3_48") (pintype "bidirectional"))
    )
    (net (code "158") (name "unconnected-(U5-SIM_DET-Pad42)") (class "Default")
      (node (ref "U5") (pin "42") (pinfunction "SIM_DET_42") (pintype "bidirectional"))
    )
    (net (code "159") (name "unconnected-(U10-DCCH-PadP$AB2)") (class "Default")
      (node (ref "U10") (pin "P$AB2") (pinfunction "DCCH_P$AB2") (pintype "bidirectional"))
    )
    (net (code "160") (name "unconnected-(U15-OC-Pad3)") (class "Default")
      (node (ref "U15") (pin "3") (pinfunction "OC_3") (pintype "output"))
    )
    (net (code "161") (name "unconnected-(USB-ID-Pad4)") (class "Default")
      (node (ref "USB") (pin "4") (pinfunction "ID_4") (pintype "bidirectional"))
    )
    (net (code "162") (name "unconnected-(XT2-Pad2)") (class "Default")
      (node (ref "XT2") (pin "2") (pinfunction "2_2") (pintype "passive"))
    )
    (net (code "163") (name "unconnected-(XT2-Pad4)") (class "Default")
      (node (ref "XT2") (pin "4") (pinfunction "4_4") (pintype "passive"))
    )
  )
)
